# Arduino_DUE_V02b_1.net
KiCad netlist of a schematic drawn in Altium Designer
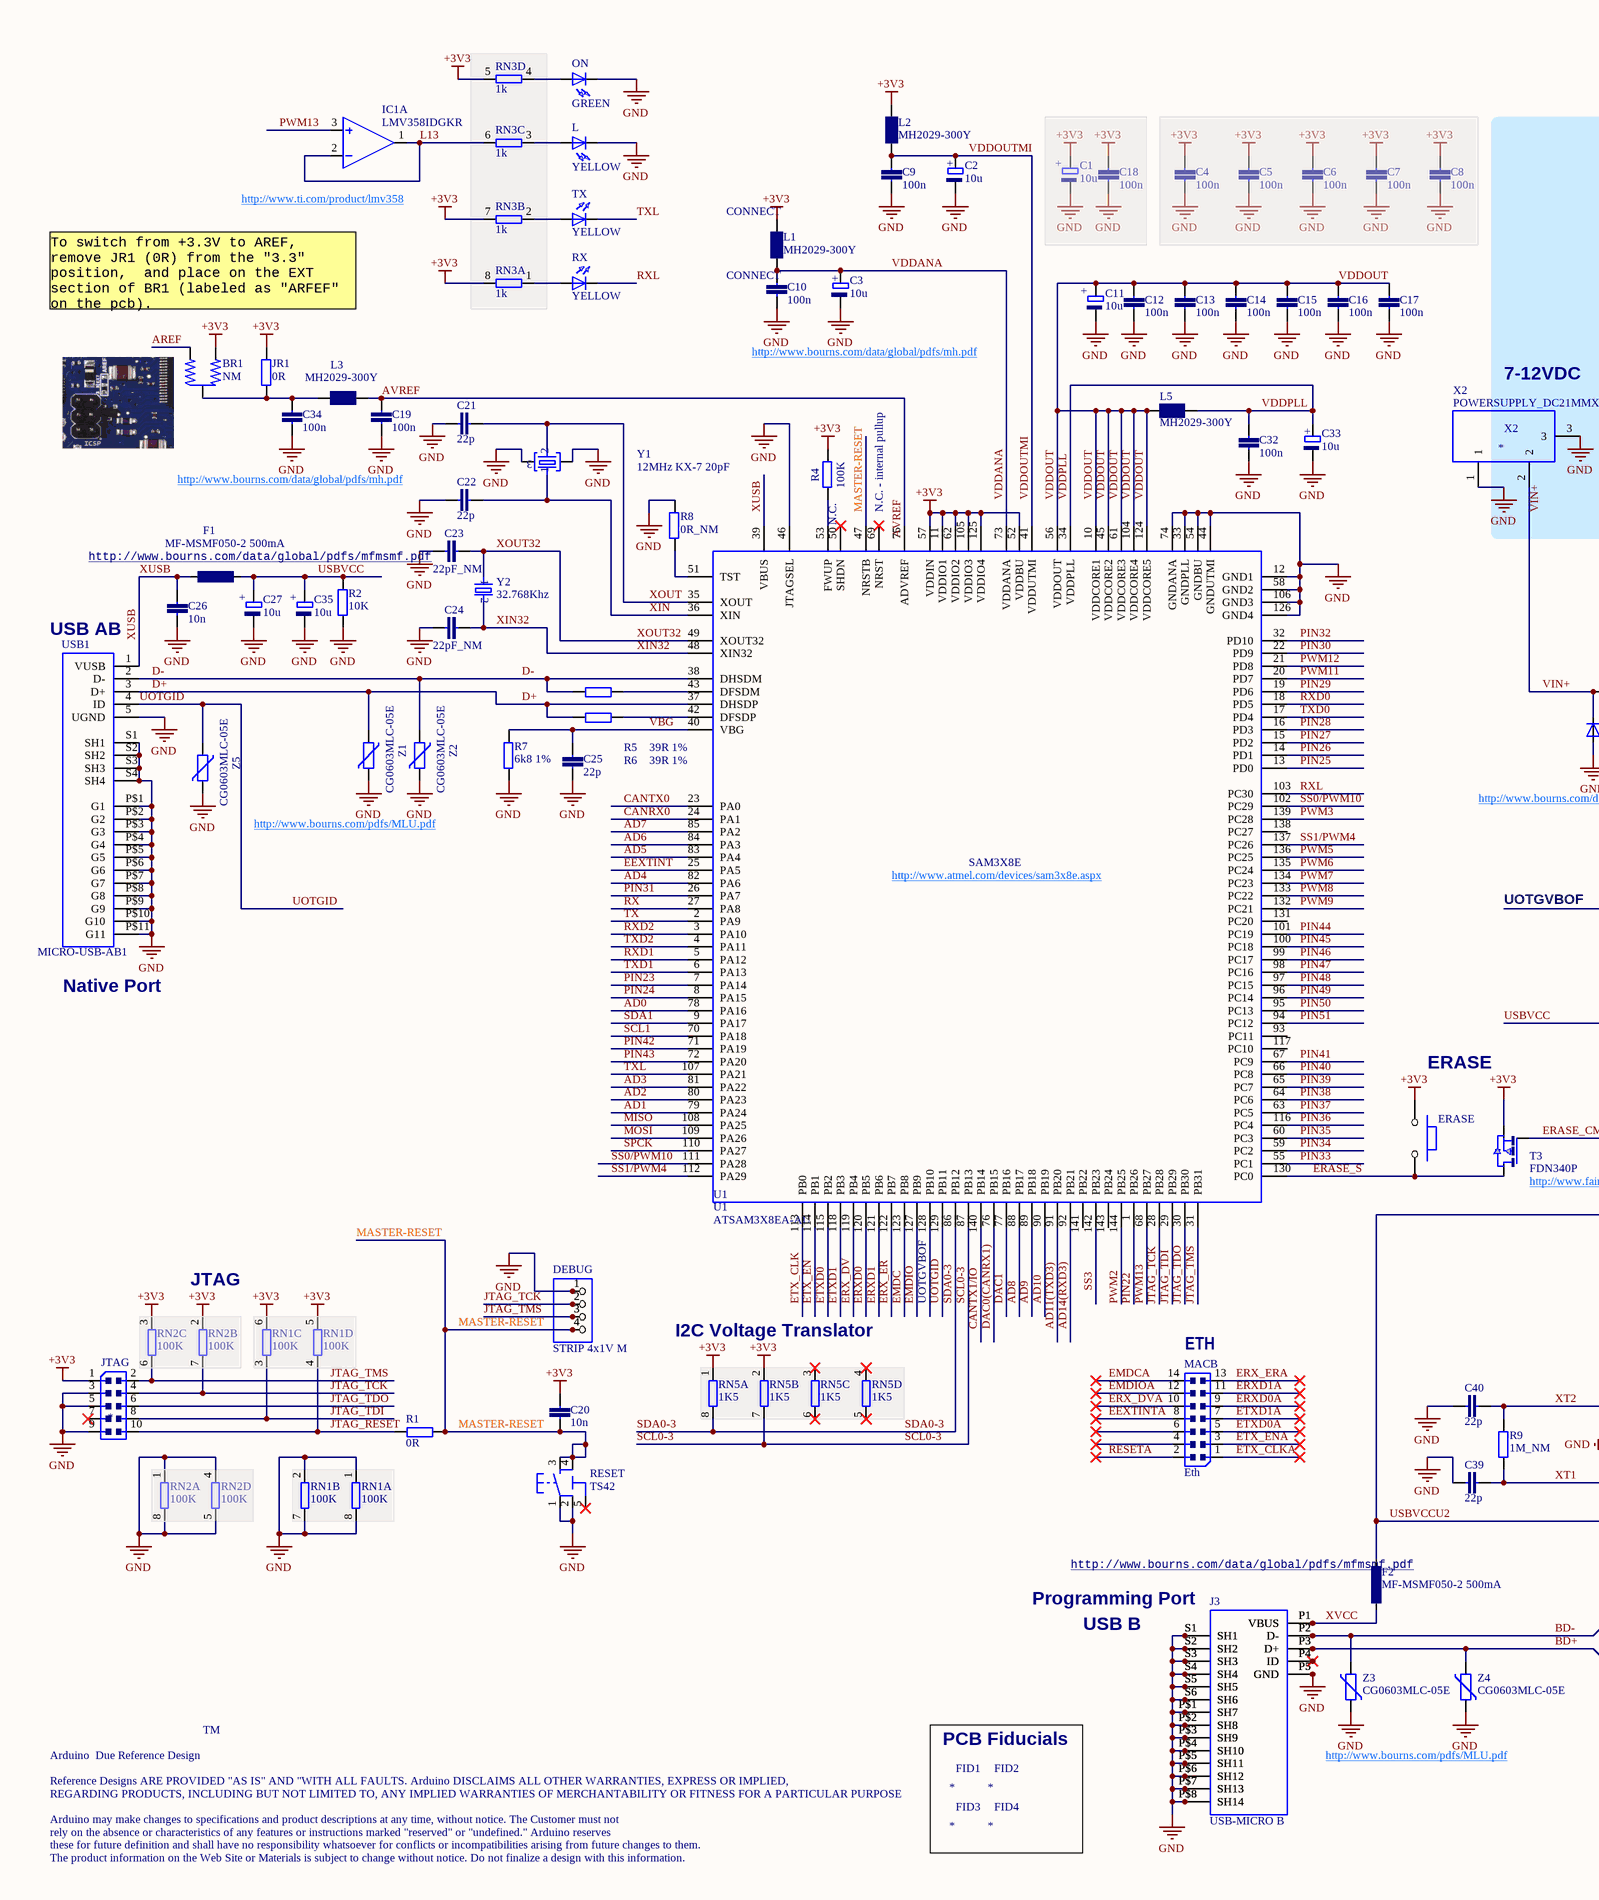
[diagram p0: Arduino_DUE_V02b_1.SchDoc, left]
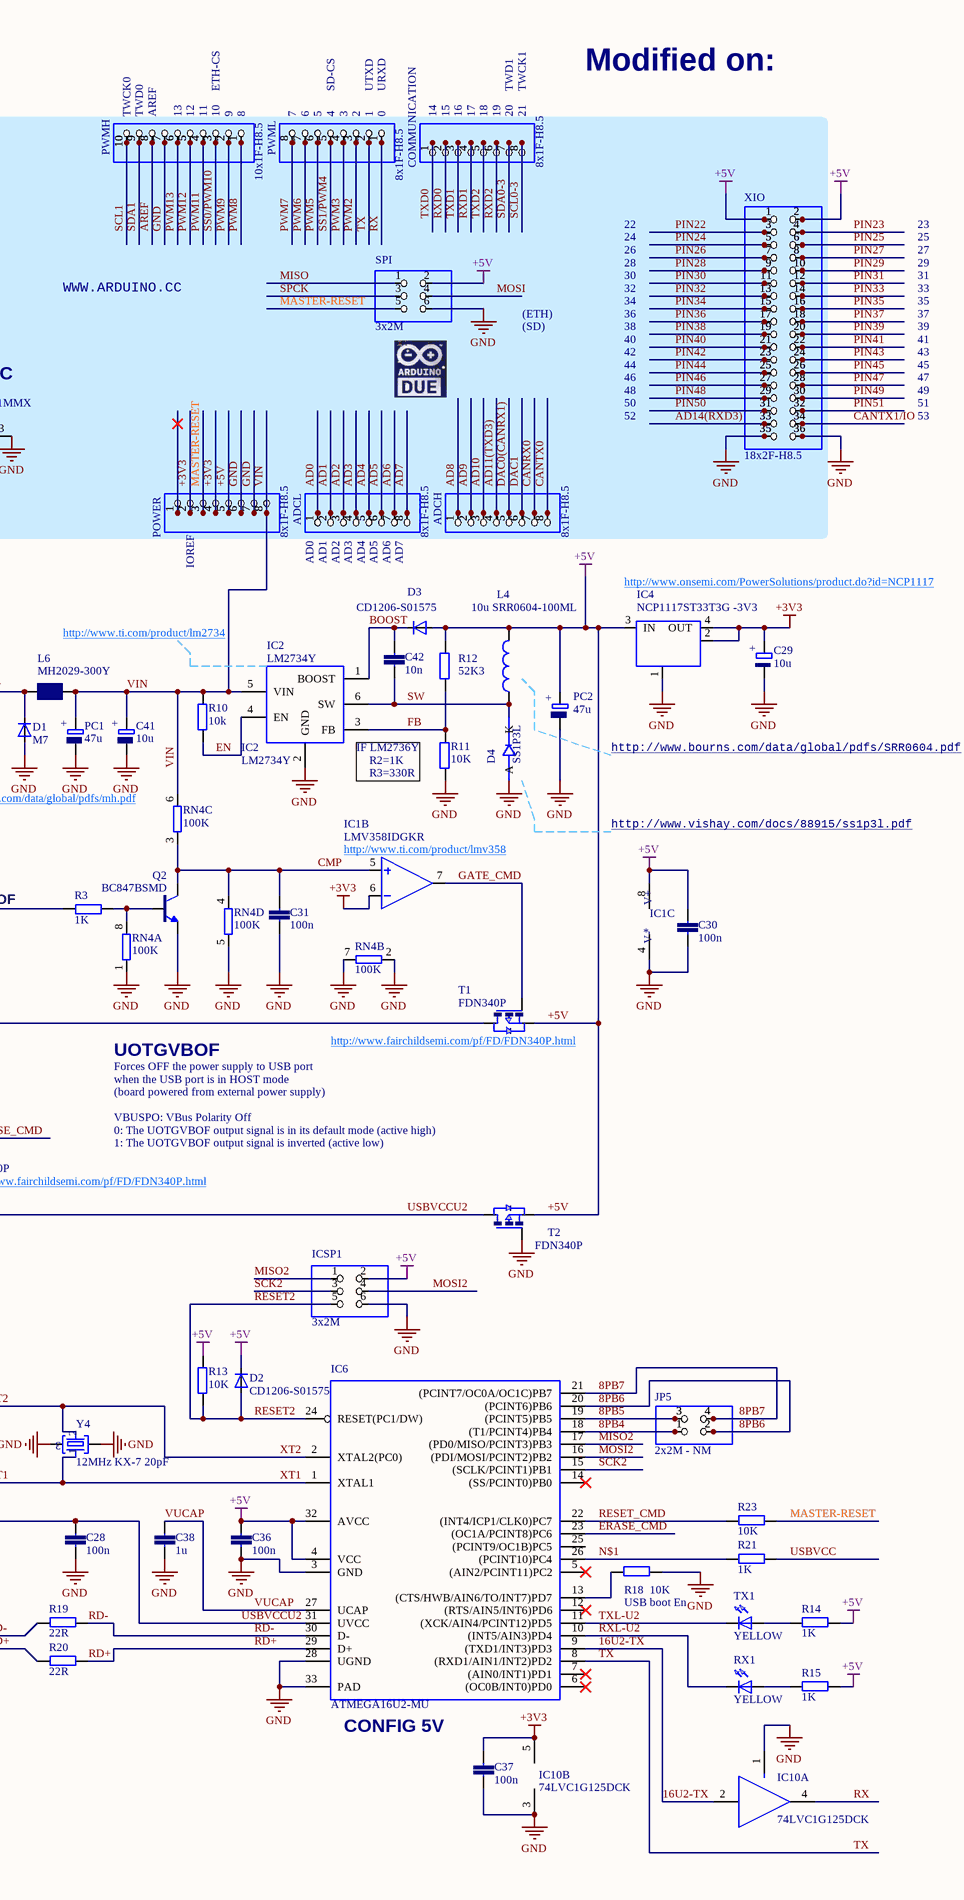
[diagram p1: Arduino_DUE_V02b_1.SchDoc, right]

(export (version "E")
  (design (tool "Eeschema 10.0.6"))
  (components
    (comp (ref "ADCH") (value "8x1F-H8.5") (footprint "1X08") (libsource (lib "SmartPrj") (part "PINHD-1X8")))
    (comp (ref "ADCL") (value "8x1F-H8.5") (footprint "1X08") (libsource (lib "SmartPrj") (part "PINHD-1X8")))
    (comp (ref "BR1") (value "NM") (footprint "J0402") (libsource (lib "bibaja") (part "J0402")))
    (comp (ref "C1") (value "10u") (footprint "SMC_B") (libsource (lib "") (part "CPOL-EUSMCB_1")))
    (comp (ref "C2") (value "10u") (footprint "SMC_B") (libsource (lib "rcl") (part "CPOL-EUSMCB")))
    (comp (ref "C3") (value "10u") (footprint "SMC_B") (libsource (lib "rcl") (part "CPOL-EUSMCB")))
    (comp (ref "C4") (value "100n") (footprint "C0402") (libsource (lib "") (part "C-EUC0402_2")))
    (comp (ref "C5") (value "100n") (footprint "C0402") (libsource (lib "") (part "C-EUC0402_2")))
    (comp (ref "C6") (value "100n") (footprint "C0402") (libsource (lib "") (part "C-EUC0402_2")))
    (comp (ref "C7") (value "100n") (footprint "C0402") (libsource (lib "") (part "C-EUC0402_2")))
    (comp (ref "C8") (value "100n") (footprint "C0402") (libsource (lib "") (part "C-EUC0402_2")))
    (comp (ref "C9") (value "100n") (footprint "C0402") (libsource (lib "") (part "C-EUC0402_2")))
    (comp (ref "C10") (value "100n") (footprint "C0402") (libsource (lib "") (part "C-EUC0402_2")))
    (comp (ref "C11") (value "10u") (footprint "SMC_B") (libsource (lib "") (part "CPOL-EUSMCB_1")))
    (comp (ref "C12") (value "100n") (footprint "C0402") (libsource (lib "") (part "C-EUC0402_2")))
    (comp (ref "C13") (value "100n") (footprint "C0402") (libsource (lib "") (part "C-EUC0402_2")))
    (comp (ref "C14") (value "100n") (footprint "C0402") (libsource (lib "") (part "C-EUC0402_2")))
    (comp (ref "C15") (value "100n") (footprint "C0402") (libsource (lib "") (part "C-EUC0402_2")))
    (comp (ref "C16") (value "100n") (footprint "C0402") (libsource (lib "") (part "C-EUC0402_2")))
    (comp (ref "C17") (value "100n") (footprint "C0402") (libsource (lib "") (part "C-EUC0402_2")))
    (comp (ref "C18") (value "100n") (footprint "C0402") (libsource (lib "") (part "C-EUC0402_2")))
    (comp (ref "C19") (value "100n") (footprint "C0402") (libsource (lib "") (part "C-EUC0402_1")))
    (comp (ref "C20") (value "10n") (footprint "C0402") (libsource (lib "") (part "C-EUC0402_1")))
    (comp (ref "C21") (value "22p") (footprint "C0402") (libsource (lib "") (part "C-EUC0402_3")))
    (comp (ref "C22") (value "22p") (footprint "C0402") (libsource (lib "") (part "C-EUC0402_3")))
    (comp (ref "C23") (value "22pF_NM") (footprint "C0402") (libsource (lib "") (part "C-EUC0402_3")))
    (comp (ref "C24") (value "22pF_NM") (footprint "C0402") (libsource (lib "") (part "C-EUC0402_3")))
    (comp (ref "C25") (value "22p") (footprint "C0402") (libsource (lib "SmartPrj") (part "C-EUC0402")))
    (comp (ref "C26") (value "10n") (footprint "C0402") (libsource (lib "SmartPrj") (part "C-EUC0402")))
    (comp (ref "C27") (value "10u") (footprint "SMC_B") (libsource (lib "") (part "CPOL-EUSMCB_1")))
    (comp (ref "C28") (value "100n") (footprint "C0402") (libsource (lib "SmartPrj") (part "C-EUC0402")))
    (comp (ref "C29") (value "10u") (footprint "SMC_B") (libsource (lib "") (part "CPOL-EUSMCB_1")))
    (comp (ref "C30") (value "100n") (footprint "C0402") (libsource (lib "") (part "C-EUC0402_2")))
    (comp (ref "C31") (value "100n") (footprint "C0402") (libsource (lib "") (part "C-EUC0402_2")))
    (comp (ref "C32") (value "100n") (footprint "C0402") (libsource (lib "") (part "C-EUC0402_2")))
    (comp (ref "C33") (value "10u") (footprint "SMC_B") (libsource (lib "rcl") (part "CPOL-EUSMCB")))
    (comp (ref "C34") (value "100n") (footprint "C0402") (libsource (lib "") (part "C-EUC0402_1")))
    (comp (ref "C35") (value "10u") (footprint "SMC_B") (libsource (lib "") (part "CPOL-EUSMCB_1")))
    (comp (ref "C36") (value "100n") (footprint "C0402") (libsource (lib "SmartPrj") (part "C-EUC0402")))
    (comp (ref "C37") (value "100n") (footprint "C0402") (libsource (lib "SmartPrj") (part "C-EUC0402")))
    (comp (ref "C38") (value "1u") (footprint "C0402") (libsource (lib "SmartPrj") (part "C-EUC0402")))
    (comp (ref "C39") (value "22p") (footprint "C0402") (libsource (lib "") (part "C-EUC0402_3")))
    (comp (ref "C40") (value "22p") (footprint "C0402") (libsource (lib "") (part "C-EUC0402_3")))
    (comp (ref "C41") (value "10u") (footprint "SMC_B") (libsource (lib "") (part "CPOL-EUSMCB_2")))
    (comp (ref "C42") (value "10n") (footprint "C0603-ROUND") (libsource (lib "SmartPrj") (part "C-EUC0603")))
    (comp (ref "COMMUNICATION")
      (value "8x1F-H8.5")
      (footprint "1X08")
      (libsource (lib "SmartPrj") (part "PINHD-1X8"))
    )
    (comp (ref "D1") (value "M7") (footprint "SMB") (libsource (lib "diode") (part "DIODE-SMB")))
    (comp (ref "D2")
      (value "CD1206-S01575")
      (footprint "MINIMELF")
      (libsource (lib "diode") (part "DIODE-MINIMELF"))
    )
    (comp (ref "D3")
      (value "CD1206-S01575")
      (footprint "MINIMELF")
      (libsource (lib "diode") (part "DIODE-MINIMELF"))
    )
    (comp (ref "D4") (value "SS1P3L") (footprint "DO220AAL") (libsource (lib "SmartPrj") (part "SS1P3L")))
    (comp (ref "DEBUG")
      (value "STRIP 4x1V M")
      (footprint "1X04")
      (libsource (lib "pinhead") (part "PINHD-1X4"))
    )
    (comp (ref "ERASE") (value "~") (footprint "SMD_157SW") (libsource (lib "SmartPrj") (part "MYSMD_PB157")))
    (comp (ref "F1")
      (value "MF-MSMF050-2 500mA")
      (footprint "L1812")
      (libsource (lib "") (part "L-EUL1812_1"))
    )
    (comp (ref "F2")
      (value "MF-MSMF050-2 500mA")
      (footprint "L1812")
      (libsource (lib "rcl") (part "L-EUL1812"))
    )
    (comp (ref "FID1")
      (value "*")
      (footprint "FIDUCIA-MOUNT")
      (libsource (lib "SmartPrj") (part "FIDUCIALMOUNT"))
    )
    (comp (ref "FID2")
      (value "*")
      (footprint "FIDUCIA-MOUNT")
      (libsource (lib "SmartPrj") (part "FIDUCIALMOUNT"))
    )
    (comp (ref "FID3")
      (value "*")
      (footprint "FIDUCIA-MOUNT")
      (libsource (lib "SmartPrj") (part "FIDUCIALMOUNT"))
    )
    (comp (ref "FID4")
      (value "*")
      (footprint "FIDUCIA-MOUNT")
      (libsource (lib "SmartPrj") (part "FIDUCIALMOUNT"))
    )
    (comp (ref "IC1")
      (value "LMV358IDGKR")
      (footprint "MSOP08")
      (libsource (lib "linear") (part "LMV358MMX"))
    )
    (comp (ref "IC2") (value "LM2734Y") (footprint "SOT23-6") (libsource (lib "SmartPrj") (part "LM2736Y")))
    (comp (ref "IC4")
      (value "NCP1117ST33T3G -3V3")
      (footprint "SOT223")
      (libsource (lib "linear") (part "MC33269ST-3.3T3"))
    )
    (comp (ref "IC6")
      (value "ATMEGA16U2-MU")
      (footprint "MLF32")
      (libsource (lib "SmartPrj") (part "ATMEGA16U2-MU"))
    )
    (comp (ref "IC10")
      (value "74LVC1G125DCK")
      (footprint "SC70-5")
      (libsource (lib "74xx-little-us") (part "74LVC1G125DCK"))
    )
    (comp (ref "ICSP1") (value "3x2M") (footprint "2X03") (libsource (lib "SmartPrj") (part "PINHD-2X3")))
    (comp (ref "J3")
      (value "USB-MICRO B")
      (footprint "CON2_USB_MICRO_B_AT")
      (libsource (lib "SmartPrj") (part "MYCON2_USB-MINI-B"))
    )
    (comp (ref "JP5") (value "2x2M - NM") (footprint "2X02") (libsource (lib "SmartPrj") (part "PINHD-2X2")))
    (comp (ref "JR1") (value "0R") (footprint "R0402") (libsource (lib "SmartPrj") (part "R-EU_R0402")))
    (comp (ref "JTAG")
      (value "*")
      (footprint "PINHEAD_2X05_127")
      (libsource (lib "Arduino_Wifi_shield_v018_tG") (part "PINHEAD_PINHD-2X5PASSO127"))
    )
    (comp (ref "L")
      (value "YELLOW")
      (footprint "CHIP-LED0805")
      (libsource (lib "") (part "LEDCHIP-LED0805_2"))
    )
    (comp (ref "L1") (value "MH2029-300Y") (footprint "0805") (libsource (lib "") (part "WE-CBF_0805_1")))
    (comp (ref "L2") (value "MH2029-300Y") (footprint "0805") (libsource (lib "") (part "WE-CBF_0805_1")))
    (comp (ref "L3") (value "MH2029-300Y") (footprint "0805") (libsource (lib "") (part "WE-CBF_0805_2")))
    (comp (ref "L4")
      (value "10u SRR0604-100ML")
      (footprint "SRR0604")
      (libsource (lib "SmartPrj") (part "L-USSRR0604"))
    )
    (comp (ref "L5") (value "MH2029-300Y") (footprint "0805") (libsource (lib "") (part "WE-CBF_0805_2")))
    (comp (ref "L6")
      (value "MH2029-300Y")
      (footprint "0805")
      (libsource (lib "wuerth-elektronik") (part "WE-CBF_0805"))
    )
    (comp (ref "MACB")
      (value "Eth")
      (footprint "PINHEAD_2X07_127")
      (libsource (lib "Arduino_Wifi_shield_v018_tG") (part "PINHEAD_PINHD-2X7PASSO127"))
    )
    (comp (ref "ON")
      (value "GREEN")
      (footprint "CHIP-LED0805")
      (libsource (lib "") (part "LEDCHIP-LED0805_2"))
    )
    (comp (ref "PC1") (value "47u") (footprint "PANASONIC_D") (libsource (lib "rcl") (part "CPOL-EUD")))
    (comp (ref "PC2") (value "47u") (footprint "PANASONIC_D") (libsource (lib "rcl") (part "CPOL-EUD")))
    (comp (ref "POWER")
      (value "8x1F-H8.5")
      (footprint "1X08")
      (libsource (lib "SmartPrj") (part "PINHD-1X8"))
    )
    (comp (ref "PWMH")
      (value "10x1F-H8.5")
      (footprint "1X10")
      (libsource (lib "SmartPrj") (part "PINHD-1X10"))
    )
    (comp (ref "PWML") (value "8x1F-H8.5") (footprint "1X08") (libsource (lib "SmartPrj") (part "PINHD-1X8")))
    (comp (ref "Q2")
      (value "BC847BSMD")
      (footprint "SOT23")
      (libsource (lib "transistor-npn") (part "BC847BSMD"))
    )
    (comp (ref "R1") (value "0R") (footprint "R0402") (libsource (lib "SmartPrj") (part "R-EU_R0402")))
    (comp (ref "R2") (value "10K") (footprint "R0402") (libsource (lib "") (part "R-EU_R0402_2")))
    (comp (ref "R3") (value "1K") (footprint "R0402") (libsource (lib "SmartPrj") (part "R-EU_R0402")))
    (comp (ref "R4") (value "100K") (footprint "R0402") (libsource (lib "") (part "R-EU_R0402_1")))
    (comp (ref "R5") (value "39R 1%") (footprint "R0402") (libsource (lib "SmartPrj") (part "R-EU_R0402")))
    (comp (ref "R6") (value "39R 1%") (footprint "R0402") (libsource (lib "SmartPrj") (part "R-EU_R0402")))
    (comp (ref "R7")
      (value "6k8 1%")
      (footprint "R0603-ROUND")
      (libsource (lib "SmartPrj") (part "R-EU_R0603"))
    )
    (comp (ref "R8") (value "0R_NM") (footprint "R0402") (libsource (lib "SmartPrj") (part "R-EU_R0402")))
    (comp (ref "R9") (value "1M_NM") (footprint "R0402") (libsource (lib "") (part "R-EU_R0402_1")))
    (comp (ref "R10") (value "10k") (footprint "R0402") (libsource (lib "SmartPrj") (part "R-EU_R0402")))
    (comp (ref "R11")
      (value "10K")
      (footprint "R0603-ROUND")
      (libsource (lib "SmartPrj") (part "R-EU_0603-RND"))
    )
    (comp (ref "R12")
      (value "52K3")
      (footprint "R0603-ROUND")
      (libsource (lib "SmartPrj") (part "R-EU_0603-RND"))
    )
    (comp (ref "R13") (value "10K") (footprint "R0402") (libsource (lib "") (part "R-EU_R0402_1")))
    (comp (ref "R14") (value "1K") (footprint "R0402") (libsource (lib "SmartPrj") (part "R-EU_R0402")))
    (comp (ref "R15") (value "1K") (footprint "R0402") (libsource (lib "SmartPrj") (part "R-EU_R0402")))
    (comp (ref "R18") (value "10K") (footprint "R0402") (libsource (lib "") (part "R-EU_R0402_1")))
    (comp (ref "R19") (value "22R") (footprint "R0402") (libsource (lib "SmartPrj") (part "R-EU_R0402")))
    (comp (ref "R20") (value "22R") (footprint "R0402") (libsource (lib "SmartPrj") (part "R-EU_R0402")))
    (comp (ref "R21") (value "1K") (footprint "R0402") (libsource (lib "") (part "R-EU_R0402_1")))
    (comp (ref "R23") (value "10K") (footprint "R0402") (libsource (lib "") (part "R-EU_R0402_1")))
    (comp (ref "RESET") (value "TS42") (footprint "TS42") (libsource (lib "SmartPrj") (part "TS42")))
    (comp (ref "RN1") (value "100K") (footprint "CAT16") (libsource (lib "") (part "4R-NCAT16_14")))
    (comp (ref "RN2") (value "100K") (footprint "CAT16") (libsource (lib "") (part "4R-NCAT16_11")))
    (comp (ref "RN3") (value "1k") (footprint "CAY16") (libsource (lib "") (part "4R-NCAY16_2")))
    (comp (ref "RN4") (value "100K") (footprint "CAT16") (libsource (lib "") (part "4R-NCAT16_9")))
    (comp (ref "RN5") (value "1K5") (footprint "CAT16") (libsource (lib "") (part "4R-NCAT16_5")))
    (comp (ref "RX")
      (value "YELLOW")
      (footprint "CHIP-LED0805")
      (libsource (lib "led") (part "LEDCHIP-LED0805"))
    )
    (comp (ref "RX1")
      (value "YELLOW")
      (footprint "CHIP-LED0805")
      (libsource (lib "") (part "LEDCHIP-LED0805_1"))
    )
    (comp (ref "SPI") (value "3x2M") (footprint "2X03") (libsource (lib "SmartPrj") (part "PINHD-2X3")))
    (comp (ref "T1") (value "FDN340P") (footprint "SOT-23") (libsource (lib "") (part "PMOSSOT23_1")))
    (comp (ref "T2") (value "FDN340P") (footprint "SOT-23") (libsource (lib "") (part "PMOSSOT23_2")))
    (comp (ref "T3") (value "FDN340P") (footprint "SOT-23") (libsource (lib "zetex") (part "PMOSSOT23")))
    (comp (ref "TX")
      (value "YELLOW")
      (footprint "CHIP-LED0805")
      (libsource (lib "led") (part "LEDCHIP-LED0805"))
    )
    (comp (ref "TX1")
      (value "YELLOW")
      (footprint "CHIP-LED0805")
      (libsource (lib "") (part "LEDCHIP-LED0805_1"))
    )
    (comp (ref "U1")
      (value "SAM3X8E")
      (footprint "LQFP144")
      (libsource (lib "SmartPrj") (part "ATSAM3X/AAU"))
    )
    (comp (ref "USB1")
      (value "MICRO-USB-AB1")
      (footprint "MCR-AB1-S-RA-SMT")
      (libsource (lib "SmartPrj") (part "MICRO_USB"))
    )
    (comp (ref "X2")
      (value "*")
      (footprint "POWERSUPPLY_DC-21MM")
      (libsource (lib "SmartPrj") (part "POWERSUPPLY_DC21MMX"))
    )
    (comp (ref "XIO")
      (value "18x2F-H8.5")
      (footprint "2X18")
      (libsource (lib "SmartPrj") (part "PINHD-2X18"))
    )
    (comp (ref "Y1")
      (value "12MHz KX-7 20pF")
      (footprint "CRYSTAL-3.2-2.5")
      (libsource (lib "SmartPrj") (part "CRYSTAL-3.2-2.5"))
    )
    (comp (ref "Y2")
      (value "32.768Khz")
      (footprint "RESONATOR_EPSON_FC_145")
      (libsource (lib "Arduino_Wifi_shield_v018_tG") (part "RESONATOR_EPSON_FC_145"))
    )
    (comp (ref "Y4")
      (value "12MHz KX-7 20pF")
      (footprint "CRYSTAL-3.2-2.5")
      (libsource (lib "") (part "CRYSTAL-3.2-2.5_1"))
    )
    (comp (ref "Z1")
      (value "CG0603MLC-05E")
      (footprint "CT/CN0603")
      (libsource (lib "") (part "VARISTORCN0603_1"))
    )
    (comp (ref "Z2")
      (value "CG0603MLC-05E")
      (footprint "CT/CN0603")
      (libsource (lib "") (part "VARISTORCN0603_1"))
    )
    (comp (ref "Z3")
      (value "CG0603MLC-05E")
      (footprint "CT/CN0603")
      (libsource (lib "varistor") (part "VARISTORCN0603"))
    )
    (comp (ref "Z4")
      (value "CG0603MLC-05E")
      (footprint "CT/CN0603")
      (libsource (lib "varistor") (part "VARISTORCN0603"))
    )
    (comp (ref "Z5")
      (value "CG0603MLC-05E")
      (footprint "CT/CN0603")
      (libsource (lib "") (part "VARISTORCN0603_1"))
    )
  )
  (nets
    (net (code "1") (name "+3V3") (class "Default")
      (node (ref "BR1") (pin "3") (pinfunction "2_3") (pintype "passive"))
      (node (ref "C1") (pin "+") (pinfunction "+_+") (pintype "passive"))
      (node (ref "C18") (pin "2") (pinfunction "2_2") (pintype "passive"))
      (node (ref "C20") (pin "2") (pinfunction "2_2") (pintype "passive"))
      (node (ref "C29") (pin "+") (pinfunction "+_+") (pintype "passive"))
      (node (ref "C37") (pin "1") (pinfunction "1_1") (pintype "passive"))
      (node (ref "C4") (pin "2") (pinfunction "2_2") (pintype "passive"))
      (node (ref "C5") (pin "2") (pinfunction "2_2") (pintype "passive"))
      (node (ref "C6") (pin "2") (pinfunction "2_2") (pintype "passive"))
      (node (ref "C7") (pin "2") (pinfunction "2_2") (pintype "passive"))
      (node (ref "C8") (pin "2") (pinfunction "2_2") (pintype "passive"))
      (node (ref "ERASE") (pin "1") (pinfunction "1_1") (pintype "passive"))
      (node (ref "IC1") (pin "6") (pinfunction "-IN_6") (pintype "passive"))
      (node (ref "IC10") (pin "5") (pinfunction "VCC_5") (pintype "passive"))
      (node (ref "IC4") (pin "2") (pinfunction "OUT@1_2") (pintype "passive"))
      (node (ref "IC4") (pin "4") (pinfunction "OUT_4") (pintype "passive"))
      (node (ref "JR1") (pin "1") (pinfunction "1_1") (pintype "passive"))
      (node (ref "JTAG") (pin "1") (pinfunction "1_1") (pintype "passive"))
      (node (ref "L1") (pin "1") (pinfunction "1_1") (pintype "passive"))
      (node (ref "L2") (pin "1") (pinfunction "1_1") (pintype "passive"))
      (node (ref "POWER") (pin "2") (pinfunction "2_2") (pintype "passive"))
      (node (ref "POWER") (pin "4") (pinfunction "4_4") (pintype "passive"))
      (node (ref "R4") (pin "2") (pinfunction "2_2") (pintype "passive"))
      (node (ref "RN1") (pin "5") (pinfunction "2_5") (pintype "passive"))
      (node (ref "RN1") (pin "6") (pinfunction "2_6") (pintype "passive"))
      (node (ref "RN2") (pin "2") (pinfunction "1_2") (pintype "passive"))
      (node (ref "RN2") (pin "3") (pinfunction "1_3") (pintype "passive"))
      (node (ref "RN3") (pin "5") (pinfunction "2_5") (pintype "passive"))
      (node (ref "RN3") (pin "7") (pinfunction "2_7") (pintype "passive"))
      (node (ref "RN3") (pin "8") (pinfunction "2_8") (pintype "passive"))
      (node (ref "RN5") (pin "1") (pinfunction "1_1") (pintype "passive"))
      (node (ref "RN5") (pin "2") (pinfunction "1_2") (pintype "passive"))
      (node (ref "T3") (pin "2") (pinfunction "S_2") (pintype "passive"))
      (node (ref "U1") (pin "105") (pinfunction "VDDIO3_105") (pintype "passive"))
      (node (ref "U1") (pin "11") (pinfunction "VDDIO1_11") (pintype "passive"))
      (node (ref "U1") (pin "125") (pinfunction "VDDIO4_125") (pintype "passive"))
      (node (ref "U1") (pin "52") (pinfunction "VDDBU_52") (pintype "passive"))
      (node (ref "U1") (pin "57") (pinfunction "VDDIN_57") (pintype "passive"))
      (node (ref "U1") (pin "62") (pinfunction "VDDIO2_62") (pintype "passive"))
    )
    (net (code "2") (name "+5V") (class "Default")
      (node (ref "C30") (pin "2") (pinfunction "2_2") (pintype "passive"))
      (node (ref "C36") (pin "1") (pinfunction "1_1") (pintype "passive"))
      (node (ref "D2") (pin "C") (pinfunction "C_C") (pintype "passive"))
      (node (ref "D3") (pin "A") (pinfunction "A_A") (pintype "passive"))
      (node (ref "IC1") (pin "8") (pinfunction "V+_8") (pintype "passive"))
      (node (ref "IC4") (pin "3") (pinfunction "IN_3") (pintype "passive"))
      (node (ref "IC6") (pin "32") (pinfunction "AVCC_32") (pintype "passive"))
      (node (ref "IC6") (pin "4") (pinfunction "VCC_4") (pintype "passive"))
      (node (ref "ICSP1") (pin "2") (pinfunction "2_2") (pintype "passive"))
      (node (ref "L4") (pin "P$2") (pinfunction "2_P$2") (pintype "passive"))
      (node (ref "PC2") (pin "+") (pinfunction "+_+") (pintype "passive"))
      (node (ref "POWER") (pin "5") (pinfunction "5_5") (pintype "passive"))
      (node (ref "R12") (pin "1") (pinfunction "1_1") (pintype "passive"))
      (node (ref "R13") (pin "2") (pinfunction "2_2") (pintype "passive"))
      (node (ref "R14") (pin "1") (pinfunction "1_1") (pintype "passive"))
      (node (ref "R15") (pin "1") (pinfunction "1_1") (pintype "passive"))
      (node (ref "SPI") (pin "2") (pinfunction "2_2") (pintype "passive"))
      (node (ref "T1") (pin "2") (pinfunction "S_2") (pintype "passive"))
      (node (ref "T2") (pin "2") (pinfunction "S_2") (pintype "passive"))
      (node (ref "XIO") (pin "1") (pinfunction "1_1") (pintype "passive"))
      (node (ref "XIO") (pin "2") (pinfunction "2_2") (pintype "passive"))
    )
    (net (code "3") (name "/8PB4") (class "Default")
      (node (ref "IC6") (pin "18") (pinfunction "(T1/PCINT4)PB4_18") (pintype "passive"))
      (node (ref "JP5") (pin "1") (pinfunction "1_1") (pintype "passive"))
    )
    (net (code "4") (name "/8PB5") (class "Default")
      (node (ref "IC6") (pin "19") (pinfunction "(PCINT5)PB5_19") (pintype "passive"))
      (node (ref "JP5") (pin "3") (pinfunction "3_3") (pintype "passive"))
    )
    (net (code "5") (name "/8PB6") (class "Default")
      (node (ref "IC6") (pin "20") (pinfunction "(PCINT6)PB6_20") (pintype "passive"))
      (node (ref "JP5") (pin "2") (pinfunction "2_2") (pintype "passive"))
    )
    (net (code "6") (name "/8PB7") (class "Default")
      (node (ref "IC6") (pin "21") (pinfunction "(PCINT7/OC0A/OC1C)PB7_21") (pintype "passive"))
      (node (ref "JP5") (pin "4") (pinfunction "4_4") (pintype "passive"))
    )
    (net (code "7") (name "/16U2-TX") (class "Default")
      (node (ref "IC10") (pin "2") (pinfunction "I_2") (pintype "passive"))
      (node (ref "IC6") (pin "9") (pinfunction "(TXD1/INT3)PD3_9") (pintype "passive"))
    )
    (net (code "8") (name "/AD0") (class "Default")
      (node (ref "ADCL") (pin "1") (pinfunction "1_1") (pintype "passive"))
      (node (ref "U1") (pin "78") (pinfunction "PA16_78") (pintype "passive"))
    )
    (net (code "9") (name "/AD1") (class "Default")
      (node (ref "ADCL") (pin "2") (pinfunction "2_2") (pintype "passive"))
      (node (ref "U1") (pin "79") (pinfunction "PA24_79") (pintype "passive"))
    )
    (net (code "10") (name "/AD2") (class "Default")
      (node (ref "ADCL") (pin "3") (pinfunction "3_3") (pintype "passive"))
      (node (ref "U1") (pin "80") (pinfunction "PA23_80") (pintype "passive"))
    )
    (net (code "11") (name "/AD3") (class "Default")
      (node (ref "ADCL") (pin "4") (pinfunction "4_4") (pintype "passive"))
      (node (ref "U1") (pin "81") (pinfunction "PA22_81") (pintype "passive"))
    )
    (net (code "12") (name "/AD4") (class "Default")
      (node (ref "ADCL") (pin "5") (pinfunction "5_5") (pintype "passive"))
      (node (ref "U1") (pin "82") (pinfunction "PA6_82") (pintype "passive"))
    )
    (net (code "13") (name "/AD5") (class "Default")
      (node (ref "ADCL") (pin "6") (pinfunction "6_6") (pintype "passive"))
      (node (ref "U1") (pin "83") (pinfunction "PA4_83") (pintype "passive"))
    )
    (net (code "14") (name "/AD6") (class "Default")
      (node (ref "ADCL") (pin "7") (pinfunction "7_7") (pintype "passive"))
      (node (ref "U1") (pin "84") (pinfunction "PA3_84") (pintype "passive"))
    )
    (net (code "15") (name "/AD7") (class "Default")
      (node (ref "ADCL") (pin "8") (pinfunction "8_8") (pintype "passive"))
      (node (ref "U1") (pin "85") (pinfunction "PA2_85") (pintype "passive"))
    )
    (net (code "16") (name "/AD8") (class "Default")
      (node (ref "ADCH") (pin "1") (pinfunction "1_1") (pintype "passive"))
      (node (ref "U1") (pin "88") (pinfunction "PB17_88") (pintype "passive"))
    )
    (net (code "17") (name "/AD9") (class "Default")
      (node (ref "ADCH") (pin "2") (pinfunction "2_2") (pintype "passive"))
      (node (ref "U1") (pin "89") (pinfunction "PB18_89") (pintype "passive"))
    )
    (net (code "18") (name "/AD10") (class "Default")
      (node (ref "ADCH") (pin "3") (pinfunction "3_3") (pintype "passive"))
      (node (ref "U1") (pin "90") (pinfunction "PB19_90") (pintype "passive"))
    )
    (net (code "19") (name "/AD11(TXD3)") (class "Default")
      (node (ref "ADCH") (pin "4") (pinfunction "4_4") (pintype "passive"))
      (node (ref "U1") (pin "91") (pinfunction "PB20_91") (pintype "passive"))
    )
    (net (code "20") (name "/AD14(RXD3)") (class "Default")
      (node (ref "U1") (pin "92") (pinfunction "PB21_92") (pintype "passive"))
      (node (ref "XIO") (pin "33") (pinfunction "33_33") (pintype "passive"))
    )
    (net (code "21") (name "/AREF") (class "Default")
      (node (ref "BR1") (pin "1") (pinfunction "1_1") (pintype "passive"))
      (node (ref "PWMH") (pin "8") (pinfunction "8_8") (pintype "passive"))
    )
    (net (code "22") (name "/AVREF") (class "Default")
      (node (ref "C19") (pin "2") (pinfunction "2_2") (pintype "passive"))
      (node (ref "L3") (pin "2") (pinfunction "2_2") (pintype "passive"))
      (node (ref "U1") (pin "75") (pinfunction "ADVREF_75") (pintype "passive"))
    )
    (net (code "23") (name "/BD+") (class "Default")
      (node (ref "J3") (pin "P3") (pinfunction "D+_P3") (pintype "passive"))
      (node (ref "R20") (pin "2") (pinfunction "2_2") (pintype "passive"))
      (node (ref "Z4") (pin "2") (pinfunction "2_2") (pintype "passive"))
    )
    (net (code "24") (name "/BD-") (class "Default")
      (node (ref "J3") (pin "P2") (pinfunction "D-_P2") (pintype "passive"))
      (node (ref "R19") (pin "2") (pinfunction "2_2") (pintype "passive"))
      (node (ref "Z3") (pin "2") (pinfunction "2_2") (pintype "passive"))
    )
    (net (code "25") (name "/BOOST") (class "Default")
      (node (ref "C42") (pin "1") (pinfunction "1_1") (pintype "passive"))
      (node (ref "D3") (pin "C") (pinfunction "C_C") (pintype "passive"))
      (node (ref "IC2") (pin "1") (pinfunction "BOOST_1") (pintype "passive"))
    )
    (net (code "26") (name "/CANRX0") (class "Default")
      (node (ref "ADCH") (pin "7") (pinfunction "7_7") (pintype "passive"))
      (node (ref "U1") (pin "24") (pinfunction "PA1_24") (pintype "passive"))
    )
    (net (code "27") (name "/CANTX0") (class "Default")
      (node (ref "ADCH") (pin "8") (pinfunction "8_8") (pintype "passive"))
      (node (ref "U1") (pin "23") (pinfunction "PA0_23") (pintype "passive"))
    )
    (net (code "28") (name "/CANTX1{slash}IO") (class "Default")
      (node (ref "U1") (pin "140") (pinfunction "PB14_140") (pintype "passive"))
      (node (ref "XIO") (pin "34") (pinfunction "34_34") (pintype "passive"))
    )
    (net (code "29") (name "/CMP") (class "Default")
      (node (ref "C31") (pin "2") (pinfunction "2_2") (pintype "passive"))
      (node (ref "IC1") (pin "5") (pinfunction "+IN_5") (pintype "passive"))
      (node (ref "Q2") (pin "3") (pinfunction "C_3") (pintype "passive"))
      (node (ref "RN4") (pin "3") (pinfunction "1_3") (pintype "passive"))
      (node (ref "RN4") (pin "4") (pinfunction "1_4") (pintype "passive"))
    )
    (net (code "30") (name "/D+") (class "Default")
      (node (ref "R6") (pin "1") (pinfunction "1_1") (pintype "passive"))
      (node (ref "U1") (pin "37") (pinfunction "DHSDP_37") (pintype "passive"))
      (node (ref "USB1") (pin "3") (pinfunction "D+_3") (pintype "passive"))
      (node (ref "Z1") (pin "1") (pinfunction "1_1") (pintype "passive"))
    )
    (net (code "31") (name "/D-") (class "Default")
      (node (ref "R5") (pin "1") (pinfunction "1_1") (pintype "passive"))
      (node (ref "U1") (pin "38") (pinfunction "DHSDM_38") (pintype "passive"))
      (node (ref "USB1") (pin "2") (pinfunction "D-_2") (pintype "passive"))
      (node (ref "Z2") (pin "1") (pinfunction "1_1") (pintype "passive"))
    )
    (net (code "32") (name "/DAC0(CANRX1)") (class "Default")
      (node (ref "ADCH") (pin "5") (pinfunction "5_5") (pintype "passive"))
      (node (ref "U1") (pin "76") (pinfunction "PB15_76") (pintype "passive"))
    )
    (net (code "33") (name "/DAC1") (class "Default")
      (node (ref "ADCH") (pin "6") (pinfunction "6_6") (pintype "passive"))
      (node (ref "U1") (pin "77") (pinfunction "PB16_77") (pintype "passive"))
    )
    (net (code "34") (name "/EEXTINT") (class "Default")
      (node (ref "U1") (pin "25") (pinfunction "PA5_25") (pintype "passive"))
    )
    (net (code "35") (name "/EEXTINTA") (class "Default")
      (node (ref "MACB") (pin "8") (pinfunction "8_8") (pintype "passive+no_connect"))
    )
    (net (code "36") (name "/EMDC") (class "Default")
      (node (ref "U1") (pin "123") (pinfunction "PB8_123") (pintype "passive"))
    )
    (net (code "37") (name "/EMDCA") (class "Default")
      (node (ref "MACB") (pin "14") (pinfunction "14_14") (pintype "passive+no_connect"))
    )
    (net (code "38") (name "/EMDIO") (class "Default")
      (node (ref "U1") (pin "127") (pinfunction "PB9_127") (pintype "passive"))
    )
    (net (code "39") (name "/EMDIOA") (class "Default")
      (node (ref "MACB") (pin "12") (pinfunction "13_12") (pintype "passive+no_connect"))
    )
    (net (code "40") (name "/EN") (class "Default")
      (node (ref "IC2") (pin "4") (pinfunction "EN_4") (pintype "passive"))
      (node (ref "R10") (pin "2") (pinfunction "2_2") (pintype "passive"))
    )
    (net (code "41") (name "/ERASE_CMD") (class "Default")
      (node (ref "IC6") (pin "23") (pinfunction "(OC1A/PCINT8)PC6_23") (pintype "passive"))
      (node (ref "T3") (pin "3") (pinfunction "G_3") (pintype "passive"))
    )
    (net (code "42") (name "/ERASE_S") (class "Default")
      (node (ref "ERASE") (pin "2") (pinfunction "2_2") (pintype "passive"))
      (node (ref "T3") (pin "1") (pinfunction "D_1") (pintype "passive"))
      (node (ref "U1") (pin "130") (pinfunction "PC0_130") (pintype "passive"))
    )
    (net (code "43") (name "/ERXD0") (class "Default")
      (node (ref "U1") (pin "120") (pinfunction "PB5_120") (pintype "passive"))
    )
    (net (code "44") (name "/ERXD0A") (class "Default")
      (node (ref "MACB") (pin "9") (pinfunction "9_9") (pintype "passive+no_connect"))
    )
    (net (code "45") (name "/ERXD1") (class "Default")
      (node (ref "U1") (pin "121") (pinfunction "PB6_121") (pintype "passive"))
    )
    (net (code "46") (name "/ERXD1A") (class "Default")
      (node (ref "MACB") (pin "11") (pinfunction "11_11") (pintype "passive+no_connect"))
    )
    (net (code "47") (name "/ERX_DV") (class "Default")
      (node (ref "U1") (pin "119") (pinfunction "PB4_119") (pintype "passive"))
    )
    (net (code "48") (name "/ERX_DVA") (class "Default")
      (node (ref "MACB") (pin "10") (pinfunction "10_10") (pintype "passive+no_connect"))
    )
    (net (code "49") (name "/ERX_ER") (class "Default")
      (node (ref "U1") (pin "122") (pinfunction "PB7_122") (pintype "passive"))
    )
    (net (code "50") (name "/ERX_ERA") (class "Default")
      (node (ref "MACB") (pin "13") (pinfunction "12_13") (pintype "passive+no_connect"))
    )
    (net (code "51") (name "/ETXD0") (class "Default")
      (node (ref "U1") (pin "115") (pinfunction "PB2_115") (pintype "passive"))
    )
    (net (code "52") (name "/ETXD0A") (class "Default")
      (node (ref "MACB") (pin "5") (pinfunction "5_5") (pintype "passive+no_connect"))
    )
    (net (code "53") (name "/ETXD1") (class "Default")
      (node (ref "U1") (pin "118") (pinfunction "PB3_118") (pintype "passive"))
    )
    (net (code "54") (name "/ETXD1A") (class "Default")
      (node (ref "MACB") (pin "7") (pinfunction "7_7") (pintype "passive+no_connect"))
    )
    (net (code "55") (name "/ETX_CLK") (class "Default")
      (node (ref "U1") (pin "113") (pinfunction "PB0_113") (pintype "passive"))
    )
    (net (code "56") (name "/ETX_CLKA") (class "Default")
      (node (ref "MACB") (pin "1") (pinfunction "1_1") (pintype "passive+no_connect"))
    )
    (net (code "57") (name "/ETX_EN") (class "Default")
      (node (ref "U1") (pin "114") (pinfunction "PB1_114") (pintype "passive"))
    )
    (net (code "58") (name "/ETX_ENA") (class "Default")
      (node (ref "MACB") (pin "3") (pinfunction "3_3") (pintype "passive+no_connect"))
    )
    (net (code "59") (name "/FB") (class "Default")
      (node (ref "IC2") (pin "3") (pinfunction "FB_3") (pintype "passive"))
      (node (ref "R11") (pin "1") (pinfunction "1_1") (pintype "passive"))
      (node (ref "R12") (pin "2") (pinfunction "2_2") (pintype "passive"))
    )
    (net (code "60") (name "/GATE_CMD") (class "Default")
      (node (ref "IC1") (pin "7") (pinfunction "OUT_7") (pintype "passive"))
      (node (ref "T1") (pin "3") (pinfunction "G_3") (pintype "passive"))
    )
    (net (code "61") (name "/JTAG_RESET") (class "Default")
      (node (ref "JTAG") (pin "10") (pinfunction "10_10") (pintype "passive"))
      (node (ref "R1") (pin "1") (pinfunction "1_1") (pintype "passive"))
      (node (ref "RN1") (pin "4") (pinfunction "1_4") (pintype "passive"))
    )
    (net (code "62") (name "/JTAG_TCK") (class "Default")
      (node (ref "DEBUG") (pin "2") (pinfunction "2_2") (pintype "passive"))
      (node (ref "JTAG") (pin "4") (pinfunction "4_4") (pintype "passive"))
      (node (ref "RN2") (pin "7") (pinfunction "2_7") (pintype "passive"))
      (node (ref "U1") (pin "28") (pinfunction "PB28_28") (pintype "passive"))
    )
    (net (code "63") (name "/JTAG_TDI") (class "Default")
      (node (ref "JTAG") (pin "8") (pinfunction "8_8") (pintype "passive"))
      (node (ref "RN1") (pin "3") (pinfunction "1_3") (pintype "passive"))
      (node (ref "U1") (pin "29") (pinfunction "PB29_29") (pintype "passive"))
    )
    (net (code "64") (name "/JTAG_TDO") (class "Default")
      (node (ref "JTAG") (pin "6") (pinfunction "6_6") (pintype "passive"))
      (node (ref "U1") (pin "30") (pinfunction "PB30_30") (pintype "passive"))
    )
    (net (code "65") (name "/JTAG_TMS") (class "Default")
      (node (ref "DEBUG") (pin "3") (pinfunction "3_3") (pintype "passive"))
      (node (ref "JTAG") (pin "2") (pinfunction "2_2") (pintype "passive"))
      (node (ref "RN2") (pin "6") (pinfunction "2_6") (pintype "passive"))
      (node (ref "U1") (pin "31") (pinfunction "PB31_31") (pintype "passive"))
    )
    (net (code "66") (name "/L13") (class "Default")
      (node (ref "IC1") (pin "1") (pinfunction "OUT_1") (pintype "passive"))
      (node (ref "IC1") (pin "2") (pinfunction "-IN_2") (pintype "passive"))
      (node (ref "RN3") (pin "6") (pinfunction "2_6") (pintype "passive"))
    )
    (net (code "67") (name "/MASTER-RESET") (class "Default")
      (node (ref "C20") (pin "1") (pinfunction "1_1") (pintype "passive"))
      (node (ref "DEBUG") (pin "4") (pinfunction "4_4") (pintype "passive"))
      (node (ref "POWER") (pin "3") (pinfunction "3_3") (pintype "passive"))
      (node (ref "R1") (pin "2") (pinfunction "2_2") (pintype "passive"))
      (node (ref "R23") (pin "2") (pinfunction "2_2") (pintype "passive"))
      (node (ref "RESET") (pin "3") (pinfunction "3_3") (pintype "passive"))
      (node (ref "RESET") (pin "4") (pinfunction "4_4") (pintype "passive"))
      (node (ref "SPI") (pin "5") (pinfunction "5_5") (pintype "passive"))
      (node (ref "U1") (pin "47") (pinfunction "NRSTB_47") (pintype "passive"))
    )
    (net (code "68") (name "/MISO") (class "Default")
      (node (ref "SPI") (pin "1") (pinfunction "1_1") (pintype "passive"))
      (node (ref "U1") (pin "108") (pinfunction "PA25_108") (pintype "passive"))
    )
    (net (code "69") (name "/MISO2") (class "Default")
      (node (ref "IC6") (pin "17") (pinfunction "(PD0/MISO/PCINT3)PB3_17") (pintype "passive"))
      (node (ref "ICSP1") (pin "1") (pinfunction "1_1") (pintype "passive"))
    )
    (net (code "70") (name "/MOSI") (class "Default")
      (node (ref "SPI") (pin "4") (pinfunction "4_4") (pintype "passive"))
      (node (ref "U1") (pin "109") (pinfunction "PA26_109") (pintype "passive"))
    )
    (net (code "71") (name "/MOSI2") (class "Default")
      (node (ref "IC6") (pin "16") (pinfunction "(PDI/MOSI/PCINT2)PB2_16") (pintype "passive"))
      (node (ref "ICSP1") (pin "4") (pinfunction "4_4") (pintype "passive"))
    )
    (net (code "72") (name "/N$1") (class "Default")
      (node (ref "IC6") (pin "26") (pinfunction "(PCINT10)PC4_26") (pintype "passive"))
      (node (ref "R21") (pin "1") (pinfunction "1_1") (pintype "passive"))
    )
    (net (code "73") (name "/PIN22") (class "Default")
      (node (ref "U1") (pin "1") (pinfunction "PB26_1") (pintype "passive"))
      (node (ref "XIO") (pin "3") (pinfunction "3_3") (pintype "passive"))
    )
    (net (code "74") (name "/PIN23") (class "Default")
      (node (ref "U1") (pin "7") (pinfunction "PA14_7") (pintype "passive"))
      (node (ref "XIO") (pin "4") (pinfunction "4_4") (pintype "passive"))
    )
    (net (code "75") (name "/PIN24") (class "Default")
      (node (ref "U1") (pin "8") (pinfunction "PA15_8") (pintype "passive"))
      (node (ref "XIO") (pin "5") (pinfunction "5_5") (pintype "passive"))
    )
    (net (code "76") (name "/PIN25") (class "Default")
      (node (ref "U1") (pin "13") (pinfunction "PD0_13") (pintype "passive"))
      (node (ref "XIO") (pin "6") (pinfunction "6_6") (pintype "passive"))
    )
    (net (code "77") (name "/PIN26") (class "Default")
      (node (ref "U1") (pin "14") (pinfunction "PD1_14") (pintype "passive"))
      (node (ref "XIO") (pin "7") (pinfunction "7_7") (pintype "passive"))
    )
    (net (code "78") (name "/PIN27") (class "Default")
      (node (ref "U1") (pin "15") (pinfunction "PD2_15") (pintype "passive"))
      (node (ref "XIO") (pin "8") (pinfunction "8_8") (pintype "passive"))
    )
    (net (code "79") (name "/PIN28") (class "Default")
      (node (ref "U1") (pin "16") (pinfunction "PD3_16") (pintype "passive"))
      (node (ref "XIO") (pin "9") (pinfunction "9_9") (pintype "passive"))
    )
    (net (code "80") (name "/PIN29") (class "Default")
      (node (ref "U1") (pin "19") (pinfunction "PD6_19") (pintype "passive"))
      (node (ref "XIO") (pin "10") (pinfunction "10_10") (pintype "passive"))
    )
    (net (code "81") (name "/PIN30") (class "Default")
      (node (ref "U1") (pin "22") (pinfunction "PD9_22") (pintype "passive"))
      (node (ref "XIO") (pin "11") (pinfunction "11_11") (pintype "passive"))
    )
    (net (code "82") (name "/PIN31") (class "Default")
      (node (ref "U1") (pin "26") (pinfunction "PA7_26") (pintype "passive"))
      (node (ref "XIO") (pin "12") (pinfunction "12_12") (pintype "passive"))
    )
    (net (code "83") (name "/PIN32") (class "Default")
      (node (ref "U1") (pin "32") (pinfunction "PD10_32") (pintype "passive"))
      (node (ref "XIO") (pin "13") (pinfunction "13_13") (pintype "passive"))
    )
    (net (code "84") (name "/PIN33") (class "Default")
      (node (ref "U1") (pin "55") (pinfunction "PC1_55") (pintype "passive"))
      (node (ref "XIO") (pin "14") (pinfunction "14_14") (pintype "passive"))
    )
    (net (code "85") (name "/PIN34") (class "Default")
      (node (ref "U1") (pin "59") (pinfunction "PC2_59") (pintype "passive"))
      (node (ref "XIO") (pin "15") (pinfunction "15_15") (pintype "passive"))
    )
    (net (code "86") (name "/PIN35") (class "Default")
      (node (ref "U1") (pin "60") (pinfunction "PC3_60") (pintype "passive"))
      (node (ref "XIO") (pin "16") (pinfunction "16_16") (pintype "passive"))
    )
    (net (code "87") (name "/PIN36") (class "Default")
      (node (ref "U1") (pin "116") (pinfunction "PC4_116") (pintype "passive"))
      (node (ref "XIO") (pin "17") (pinfunction "17_17") (pintype "passive"))
    )
    (net (code "88") (name "/PIN37") (class "Default")
      (node (ref "U1") (pin "63") (pinfunction "PC5_63") (pintype "passive"))
      (node (ref "XIO") (pin "18") (pinfunction "18_18") (pintype "passive"))
    )
    (net (code "89") (name "/PIN38") (class "Default")
      (node (ref "U1") (pin "64") (pinfunction "PC6_64") (pintype "passive"))
      (node (ref "XIO") (pin "19") (pinfunction "19_19") (pintype "passive"))
    )
    (net (code "90") (name "/PIN39") (class "Default")
      (node (ref "U1") (pin "65") (pinfunction "PC7_65") (pintype "passive"))
      (node (ref "XIO") (pin "20") (pinfunction "20_20") (pintype "passive"))
    )
    (net (code "91") (name "/PIN40") (class "Default")
      (node (ref "U1") (pin "66") (pinfunction "PC8_66") (pintype "passive"))
      (node (ref "XIO") (pin "21") (pinfunction "21_21") (pintype "passive"))
    )
    (net (code "92") (name "/PIN41") (class "Default")
      (node (ref "U1") (pin "67") (pinfunction "PC9_67") (pintype "passive"))
      (node (ref "XIO") (pin "22") (pinfunction "22_22") (pintype "passive"))
    )
    (net (code "93") (name "/PIN42") (class "Default")
      (node (ref "U1") (pin "71") (pinfunction "PA19_71") (pintype "passive"))
      (node (ref "XIO") (pin "23") (pinfunction "23_23") (pintype "passive"))
    )
    (net (code "94") (name "/PIN43") (class "Default")
      (node (ref "U1") (pin "72") (pinfunction "PA20_72") (pintype "passive"))
      (node (ref "XIO") (pin "24") (pinfunction "24_24") (pintype "passive"))
    )
    (net (code "95") (name "/PIN44") (class "Default")
      (node (ref "U1") (pin "101") (pinfunction "PC19_101") (pintype "passive"))
      (node (ref "XIO") (pin "25") (pinfunction "25_25") (pintype "passive"))
    )
    (net (code "96") (name "/PIN45") (class "Default")
      (node (ref "U1") (pin "100") (pinfunction "PC18_100") (pintype "passive"))
      (node (ref "XIO") (pin "26") (pinfunction "26_26") (pintype "passive"))
    )
    (net (code "97") (name "/PIN46") (class "Default")
      (node (ref "U1") (pin "99") (pinfunction "PC17_99") (pintype "passive"))
      (node (ref "XIO") (pin "27") (pinfunction "27_27") (pintype "passive"))
    )
    (net (code "98") (name "/PIN47") (class "Default")
      (node (ref "U1") (pin "98") (pinfunction "PC16_98") (pintype "passive"))
      (node (ref "XIO") (pin "28") (pinfunction "28_28") (pintype "passive"))
    )
    (net (code "99") (name "/PIN48") (class "Default")
      (node (ref "U1") (pin "97") (pinfunction "PC15_97") (pintype "passive"))
      (node (ref "XIO") (pin "29") (pinfunction "29_29") (pintype "passive"))
    )
    (net (code "100") (name "/PIN49") (class "Default")
      (node (ref "U1") (pin "96") (pinfunction "PC14_96") (pintype "passive"))
      (node (ref "XIO") (pin "30") (pinfunction "30_30") (pintype "passive"))
    )
    (net (code "101") (name "/PIN50") (class "Default")
      (node (ref "U1") (pin "95") (pinfunction "PC13_95") (pintype "passive"))
      (node (ref "XIO") (pin "31") (pinfunction "31_31") (pintype "passive"))
    )
    (net (code "102") (name "/PIN51") (class "Default")
      (node (ref "U1") (pin "94") (pinfunction "PC12_94") (pintype "passive"))
      (node (ref "XIO") (pin "32") (pinfunction "32_32") (pintype "passive"))
    )
    (net (code "103") (name "/PWM2") (class "Default")
      (node (ref "PWML") (pin "3") (pinfunction "3_3") (pintype "passive"))
      (node (ref "U1") (pin "144") (pinfunction "PB25_144") (pintype "passive"))
    )
    (net (code "104") (name "/PWM3") (class "Default")
      (node (ref "PWML") (pin "4") (pinfunction "4_4") (pintype "passive"))
      (node (ref "U1") (pin "139") (pinfunction "PC28_139") (pintype "passive"))
    )
    (net (code "105") (name "/PWM5") (class "Default")
      (node (ref "PWML") (pin "6") (pinfunction "6_6") (pintype "passive"))
      (node (ref "U1") (pin "136") (pinfunction "PC25_136") (pintype "passive"))
    )
    (net (code "106") (name "/PWM6") (class "Default")
      (node (ref "PWML") (pin "7") (pinfunction "7_7") (pintype "passive"))
      (node (ref "U1") (pin "135") (pinfunction "PC24_135") (pintype "passive"))
    )
    (net (code "107") (name "/PWM7") (class "Default")
      (node (ref "PWML") (pin "8") (pinfunction "8_8") (pintype "passive"))
      (node (ref "U1") (pin "134") (pinfunction "PC23_134") (pintype "passive"))
    )
    (net (code "108") (name "/PWM8") (class "Default")
      (node (ref "PWMH") (pin "1") (pinfunction "1_1") (pintype "passive"))
      (node (ref "U1") (pin "133") (pinfunction "PC22_133") (pintype "passive"))
    )
    (net (code "109") (name "/PWM9") (class "Default")
      (node (ref "PWMH") (pin "2") (pinfunction "2_2") (pintype "passive"))
      (node (ref "U1") (pin "132") (pinfunction "PC21_132") (pintype "passive"))
    )
    (net (code "110") (name "/PWM11") (class "Default")
      (node (ref "PWMH") (pin "4") (pinfunction "4_4") (pintype "passive"))
      (node (ref "U1") (pin "20") (pinfunction "PD7_20") (pintype "passive"))
    )
    (net (code "111") (name "/PWM12") (class "Default")
      (node (ref "PWMH") (pin "5") (pinfunction "5_5") (pintype "passive"))
      (node (ref "U1") (pin "21") (pinfunction "PD8_21") (pintype "passive"))
    )
    (net (code "112") (name "/PWM13") (class "Default")
      (node (ref "IC1") (pin "3") (pinfunction "+IN_3") (pintype "passive"))
      (node (ref "PWMH") (pin "6") (pinfunction "6_6") (pintype "passive"))
      (node (ref "U1") (pin "68") (pinfunction "PB27_68") (pintype "passive"))
    )
    (net (code "113") (name "/RD+") (class "Default")
      (node (ref "IC6") (pin "29") (pinfunction "D+_29") (pintype "passive"))
      (node (ref "R20") (pin "1") (pinfunction "1_1") (pintype "passive"))
    )
    (net (code "114") (name "/RD-") (class "Default")
      (node (ref "IC6") (pin "30") (pinfunction "D-_30") (pintype "passive"))
      (node (ref "R19") (pin "1") (pinfunction "1_1") (pintype "passive"))
    )
    (net (code "115") (name "/RESET2") (class "Default")
      (node (ref "D2") (pin "A") (pinfunction "A_A") (pintype "passive"))
      (node (ref "IC6") (pin "24") (pinfunction "RESET(PC1/DW)_24") (pintype "passive"))
      (node (ref "ICSP1") (pin "5") (pinfunction "5_5") (pintype "passive"))
      (node (ref "R13") (pin "1") (pinfunction "1_1") (pintype "passive"))
    )
    (net (code "116") (name "/RESETA") (class "Default")
      (node (ref "MACB") (pin "2") (pinfunction "2_2") (pintype "passive+no_connect"))
    )
    (net (code "117") (name "/RESET_CMD") (class "Default")
      (node (ref "IC6") (pin "22") (pinfunction "(INT4/ICP1/CLK0)PC7_22") (pintype "passive"))
      (node (ref "R23") (pin "1") (pinfunction "1_1") (pintype "passive"))
    )
    (net (code "118") (name "/RX") (class "Default")
      (node (ref "IC10") (pin "4") (pinfunction "O_4") (pintype "passive"))
      (node (ref "PWML") (pin "1") (pinfunction "1_1") (pintype "passive"))
      (node (ref "U1") (pin "27") (pinfunction "PA8_27") (pintype "passive"))
    )
    (net (code "119") (name "/RXD0") (class "Default")
      (node (ref "COMMUNICATION") (pin "2") (pinfunction "2_2") (pintype "passive"))
      (node (ref "U1") (pin "18") (pinfunction "PD5_18") (pintype "passive"))
    )
    (net (code "120") (name "/RXD1") (class "Default")
      (node (ref "COMMUNICATION") (pin "4") (pinfunction "4_4") (pintype "passive"))
      (node (ref "U1") (pin "5") (pinfunction "PA12_5") (pintype "passive"))
    )
    (net (code "121") (name "/RXD2") (class "Default")
      (node (ref "COMMUNICATION") (pin "6") (pinfunction "6_6") (pintype "passive"))
      (node (ref "U1") (pin "3") (pinfunction "PA10_3") (pintype "passive"))
    )
    (net (code "122") (name "/RXL") (class "Default")
      (node (ref "RX") (pin "C") (pinfunction "C_C") (pintype "passive"))
      (node (ref "U1") (pin "103") (pinfunction "PC30_103") (pintype "passive"))
    )
    (net (code "123") (name "/RXL-U2") (class "Default")
      (node (ref "IC6") (pin "10") (pinfunction "(INT5/AIN3)PD4_10") (pintype "passive"))
      (node (ref "RX1") (pin "C") (pinfunction "C_C") (pintype "passive"))
    )
    (net (code "124") (name "/SCK2") (class "Default")
      (node (ref "IC6") (pin "15") (pinfunction "(SCLK/PCINT1)PB1_15") (pintype "passive"))
      (node (ref "ICSP1") (pin "3") (pinfunction "3_3") (pintype "passive"))
    )
    (net (code "125") (name "/SCL0-3") (class "Default")
      (node (ref "COMMUNICATION") (pin "8") (pinfunction "8_8") (pintype "passive"))
      (node (ref "RN5") (pin "7") (pinfunction "2_7") (pintype "passive"))
      (node (ref "U1") (pin "87") (pinfunction "PB13_87") (pintype "passive"))
    )
    (net (code "126") (name "/SCL1") (class "Default")
      (node (ref "PWMH") (pin "10") (pinfunction "10_10") (pintype "passive"))
      (node (ref "U1") (pin "70") (pinfunction "PA18_70") (pintype "passive"))
    )
    (net (code "127") (name "/SDA0-3") (class "Default")
      (node (ref "COMMUNICATION") (pin "7") (pinfunction "7_7") (pintype "passive"))
      (node (ref "RN5") (pin "8") (pinfunction "2_8") (pintype "passive"))
      (node (ref "U1") (pin "86") (pinfunction "PB12_86") (pintype "passive"))
    )
    (net (code "128") (name "/SDA1") (class "Default")
      (node (ref "PWMH") (pin "9") (pinfunction "9_9") (pintype "passive"))
      (node (ref "U1") (pin "9") (pinfunction "PA17_9") (pintype "passive"))
    )
    (net (code "129") (name "/SPCK") (class "Default")
      (node (ref "SPI") (pin "3") (pinfunction "3_3") (pintype "passive"))
      (node (ref "U1") (pin "110") (pinfunction "PA27_110") (pintype "passive"))
    )
    (net (code "130") (name "/SS0{slash}PWM10") (class "Default")
      (node (ref "PWMH") (pin "3") (pinfunction "3_3") (pintype "passive"))
      (node (ref "U1") (pin "102") (pinfunction "PC29_102") (pintype "passive"))
      (node (ref "U1") (pin "111") (pinfunction "PA28_111") (pintype "passive"))
    )
    (net (code "131") (name "/SS1{slash}PWM4") (class "Default")
      (node (ref "PWML") (pin "5") (pinfunction "5_5") (pintype "passive"))
      (node (ref "U1") (pin "112") (pinfunction "PA29_112") (pintype "passive"))
      (node (ref "U1") (pin "137") (pinfunction "PC26_137") (pintype "passive"))
    )
    (net (code "132") (name "/SS3") (class "Default")
      (node (ref "U1") (pin "142") (pinfunction "PB23_142") (pintype "passive"))
    )
    (net (code "133") (name "/SW") (class "Default")
      (node (ref "C42") (pin "2") (pinfunction "2_2") (pintype "passive"))
      (node (ref "D4") (pin "P$1") (pinfunction "K_P$1") (pintype "passive"))
      (node (ref "IC2") (pin "6") (pinfunction "SW_6") (pintype "passive"))
      (node (ref "L4") (pin "P$1") (pinfunction "1_P$1") (pintype "passive"))
    )
    (net (code "134") (name "/TX") (class "Default")
      (node (ref "IC6") (pin "8") (pinfunction "(RXD1/AIN1/INT2)PD2_8") (pintype "passive"))
      (node (ref "PWML") (pin "2") (pinfunction "2_2") (pintype "passive"))
      (node (ref "U1") (pin "2") (pinfunction "PA9_2") (pintype "passive"))
    )
    (net (code "135") (name "/TXD0") (class "Default")
      (node (ref "COMMUNICATION") (pin "1") (pinfunction "1_1") (pintype "passive"))
      (node (ref "U1") (pin "17") (pinfunction "PD4_17") (pintype "passive"))
    )
    (net (code "136") (name "/TXD1") (class "Default")
      (node (ref "COMMUNICATION") (pin "3") (pinfunction "3_3") (pintype "passive"))
      (node (ref "U1") (pin "6") (pinfunction "PA13_6") (pintype "passive"))
    )
    (net (code "137") (name "/TXD2") (class "Default")
      (node (ref "COMMUNICATION") (pin "5") (pinfunction "5_5") (pintype "passive"))
      (node (ref "U1") (pin "4") (pinfunction "PA11_4") (pintype "passive"))
    )
    (net (code "138") (name "/TXL") (class "Default")
      (node (ref "TX") (pin "C") (pinfunction "C_C") (pintype "passive"))
      (node (ref "U1") (pin "107") (pinfunction "PA21_107") (pintype "passive"))
    )
    (net (code "139") (name "/TXL-U2") (class "Default")
      (node (ref "IC6") (pin "11") (pinfunction "(XCK/AIN4/PCINT12)PD5_11") (pintype "passive"))
      (node (ref "TX1") (pin "C") (pinfunction "C_C") (pintype "passive"))
    )
    (net (code "140") (name "/UOTGID") (class "Default")
      (node (ref "U1") (pin "129") (pinfunction "PB11_129") (pintype "passive"))
      (node (ref "USB1") (pin "4") (pinfunction "ID_4") (pintype "passive"))
      (node (ref "Z5") (pin "2") (pinfunction "2_2") (pintype "passive"))
    )
    (net (code "141") (name "/UOTGVBOF") (class "Default")
      (node (ref "R3") (pin "1") (pinfunction "1_1") (pintype "passive"))
      (node (ref "U1") (pin "128") (pinfunction "PB10_128") (pintype "passive"))
    )
    (net (code "142") (name "/USBVCC") (class "Default")
      (node (ref "C27") (pin "+") (pinfunction "+_+") (pintype "passive"))
      (node (ref "C35") (pin "+") (pinfunction "+_+") (pintype "passive"))
      (node (ref "F1") (pin "1") (pinfunction "1_1") (pintype "passive"))
      (node (ref "R2") (pin "2") (pinfunction "2_2") (pintype "passive"))
      (node (ref "R21") (pin "2") (pinfunction "2_2") (pintype "passive"))
      (node (ref "T1") (pin "1") (pinfunction "D_1") (pintype "passive"))
    )
    (net (code "143") (name "/USBVCCU2") (class "Default")
      (node (ref "C28") (pin "1") (pinfunction "1_1") (pintype "passive"))
      (node (ref "F2") (pin "1") (pinfunction "1_1") (pintype "passive"))
      (node (ref "IC6") (pin "31") (pinfunction "UVCC_31") (pintype "passive"))
      (node (ref "T2") (pin "1") (pinfunction "D_1") (pintype "passive"))
    )
    (net (code "144") (name "/VBG") (class "Default")
      (node (ref "C25") (pin "1") (pinfunction "1_1") (pintype "passive"))
      (node (ref "R7") (pin "2") (pinfunction "2_2") (pintype "passive"))
      (node (ref "U1") (pin "40") (pinfunction "VBG_40") (pintype "passive"))
    )
    (net (code "145") (name "/VDDANA") (class "Default")
      (node (ref "C10") (pin "2") (pinfunction "2_2") (pintype "passive"))
      (node (ref "C3") (pin "+") (pinfunction "+_+") (pintype "passive"))
      (node (ref "L1") (pin "2") (pinfunction "2_2") (pintype "passive"))
      (node (ref "U1") (pin "73") (pinfunction "VDDANA_73") (pintype "passive"))
    )
    (net (code "146") (name "/VDDOUT") (class "Default")
      (node (ref "C11") (pin "+") (pinfunction "+_+") (pintype "passive"))
      (node (ref "C12") (pin "2") (pinfunction "2_2") (pintype "passive"))
      (node (ref "C13") (pin "2") (pinfunction "2_2") (pintype "passive"))
      (node (ref "C14") (pin "2") (pinfunction "2_2") (pintype "passive"))
      (node (ref "C15") (pin "2") (pinfunction "2_2") (pintype "passive"))
      (node (ref "C16") (pin "2") (pinfunction "2_2") (pintype "passive"))
      (node (ref "C17") (pin "2") (pinfunction "2_2") (pintype "passive"))
      (node (ref "L5") (pin "1") (pinfunction "1_1") (pintype "passive"))
      (node (ref "U1") (pin "10") (pinfunction "VDDCORE1_10") (pintype "passive"))
      (node (ref "U1") (pin "104") (pinfunction "VDDCORE4_104") (pintype "passive"))
      (node (ref "U1") (pin "124") (pinfunction "VDDCORE5_124") (pintype "passive"))
      (node (ref "U1") (pin "45") (pinfunction "VDDCORE2_45") (pintype "passive"))
      (node (ref "U1") (pin "56") (pinfunction "VDDOUT_56") (pintype "passive"))
      (node (ref "U1") (pin "61") (pinfunction "VDDCORE3_61") (pintype "passive"))
    )
    (net (code "147") (name "/VDDOUTMI") (class "Default")
      (node (ref "C2") (pin "+") (pinfunction "+_+") (pintype "passive"))
      (node (ref "C9") (pin "2") (pinfunction "2_2") (pintype "passive"))
      (node (ref "L2") (pin "2") (pinfunction "2_2") (pintype "passive"))
      (node (ref "U1") (pin "41") (pinfunction "VDDUTMI_41") (pintype "passive"))
    )
    (net (code "148") (name "/VDDPLL") (class "Default")
      (node (ref "C32") (pin "2") (pinfunction "2_2") (pintype "passive"))
      (node (ref "C33") (pin "+") (pinfunction "+_+") (pintype "passive"))
      (node (ref "L5") (pin "2") (pinfunction "2_2") (pintype "passive"))
      (node (ref "U1") (pin "34") (pinfunction "VDDPLL_34") (pintype "passive"))
    )
    (net (code "149") (name "/VIN") (class "Default")
      (node (ref "C41") (pin "+") (pinfunction "+_+") (pintype "passive"))
      (node (ref "IC2") (pin "5") (pinfunction "VIN_5") (pintype "passive"))
      (node (ref "L6") (pin "1") (pinfunction "1_1") (pintype "passive"))
      (node (ref "PC1") (pin "+") (pinfunction "+_+") (pintype "passive"))
      (node (ref "POWER") (pin "8") (pinfunction "8_8") (pintype "passive"))
      (node (ref "R10") (pin "1") (pinfunction "1_1") (pintype "passive"))
      (node (ref "RN4") (pin "6") (pinfunction "2_6") (pintype "passive"))
    )
    (net (code "150") (name "/VIN+") (class "Default")
      (node (ref "D1") (pin "C") (pinfunction "C_C") (pintype "passive"))
      (node (ref "L6") (pin "2") (pinfunction "2_2") (pintype "passive"))
      (node (ref "X2") (pin "2") (pinfunction "2_2") (pintype "passive"))
    )
    (net (code "151") (name "/VUCAP") (class "Default")
      (node (ref "C38") (pin "1") (pinfunction "1_1") (pintype "passive"))
      (node (ref "IC6") (pin "27") (pinfunction "UCAP_27") (pintype "passive"))
    )
    (net (code "152") (name "/XIN") (class "Default")
      (node (ref "C22") (pin "1") (pinfunction "1_1") (pintype "passive"))
      (node (ref "U1") (pin "36") (pinfunction "XIN_36") (pintype "passive"))
      (node (ref "Y1") (pin "1") (pinfunction "C1_1") (pintype "passive"))
    )
    (net (code "153") (name "/XIN32") (class "Default")
      (node (ref "C24") (pin "1") (pinfunction "1_1") (pintype "passive"))
      (node (ref "U1") (pin "48") (pinfunction "XIN32_48") (pintype "passive"))
      (node (ref "Y2") (pin "P$2") (pinfunction "2_P$2") (pintype "passive"))
    )
    (net (code "154") (name "/XOUT") (class "Default")
      (node (ref "C21") (pin "1") (pinfunction "1_1") (pintype "passive"))
      (node (ref "U1") (pin "35") (pinfunction "XOUT_35") (pintype "passive"))
      (node (ref "Y1") (pin "3") (pinfunction "C2_3") (pintype "passive"))
    )
    (net (code "155") (name "/XOUT32") (class "Default")
      (node (ref "C23") (pin "1") (pinfunction "1_1") (pintype "passive"))
      (node (ref "U1") (pin "49") (pinfunction "XOUT32_49") (pintype "passive"))
      (node (ref "Y2") (pin "P$1") (pinfunction "1_P$1") (pintype "passive"))
    )
    (net (code "156") (name "/XT1") (class "Default")
      (node (ref "C39") (pin "1") (pinfunction "1_1") (pintype "passive"))
      (node (ref "IC6") (pin "1") (pinfunction "XTAL1_1") (pintype "passive"))
      (node (ref "R9") (pin "1") (pinfunction "1_1") (pintype "passive"))
      (node (ref "Y4") (pin "1") (pinfunction "C1_1") (pintype "passive"))
    )
    (net (code "157") (name "/XT2") (class "Default")
      (node (ref "C40") (pin "1") (pinfunction "1_1") (pintype "passive"))
      (node (ref "IC6") (pin "2") (pinfunction "XTAL2(PC0)_2") (pintype "passive"))
      (node (ref "R9") (pin "2") (pinfunction "2_2") (pintype "passive"))
      (node (ref "Y4") (pin "3") (pinfunction "C2_3") (pintype "passive"))
    )
    (net (code "158") (name "/XUSB") (class "Default")
      (node (ref "C26") (pin "1") (pinfunction "1_1") (pintype "passive"))
      (node (ref "F1") (pin "2") (pinfunction "2_2") (pintype "passive"))
      (node (ref "U1") (pin "39") (pinfunction "VBUS_39") (pintype "passive"))
      (node (ref "USB1") (pin "1") (pinfunction "VUSB_1") (pintype "passive"))
    )
    (net (code "159") (name "/XVCC") (class "Default")
      (node (ref "F2") (pin "2") (pinfunction "2_2") (pintype "passive"))
      (node (ref "J3") (pin "P1") (pinfunction "VBUS_P1") (pintype "passive"))
    )
    (net (code "160") (name "GND") (class "Default")
      (node (ref "C1") (pin "-") (pinfunction "-_-") (pintype "passive"))
      (node (ref "C10") (pin "1") (pinfunction "1_1") (pintype "passive"))
      (node (ref "C11") (pin "-") (pinfunction "-_-") (pintype "passive"))
      (node (ref "C12") (pin "1") (pinfunction "1_1") (pintype "passive"))
      (node (ref "C13") (pin "1") (pinfunction "1_1") (pintype "passive"))
      (node (ref "C14") (pin "1") (pinfunction "1_1") (pintype "passive"))
      (node (ref "C15") (pin "1") (pinfunction "1_1") (pintype "passive"))
      (node (ref "C16") (pin "1") (pinfunction "1_1") (pintype "passive"))
      (node (ref "C17") (pin "1") (pinfunction "1_1") (pintype "passive"))
      (node (ref "C18") (pin "1") (pinfunction "1_1") (pintype "passive"))
      (node (ref "C19") (pin "1") (pinfunction "1_1") (pintype "passive"))
      (node (ref "C2") (pin "-") (pinfunction "-_-") (pintype "passive"))
      (node (ref "C21") (pin "2") (pinfunction "2_2") (pintype "passive"))
      (node (ref "C22") (pin "2") (pinfunction "2_2") (pintype "passive"))
      (node (ref "C23") (pin "2") (pinfunction "2_2") (pintype "passive"))
      (node (ref "C24") (pin "2") (pinfunction "2_2") (pintype "passive"))
      (node (ref "C25") (pin "2") (pinfunction "2_2") (pintype "passive"))
      (node (ref "C26") (pin "2") (pinfunction "2_2") (pintype "passive"))
      (node (ref "C27") (pin "-") (pinfunction "-_-") (pintype "passive"))
      (node (ref "C28") (pin "2") (pinfunction "2_2") (pintype "passive"))
      (node (ref "C29") (pin "-") (pinfunction "-_-") (pintype "passive"))
      (node (ref "C3") (pin "-") (pinfunction "-_-") (pintype "passive"))
      (node (ref "C30") (pin "1") (pinfunction "1_1") (pintype "passive"))
      (node (ref "C31") (pin "1") (pinfunction "1_1") (pintype "passive"))
      (node (ref "C32") (pin "1") (pinfunction "1_1") (pintype "passive"))
      (node (ref "C33") (pin "-") (pinfunction "-_-") (pintype "passive"))
      (node (ref "C34") (pin "1") (pinfunction "1_1") (pintype "passive"))
      (node (ref "C35") (pin "-") (pinfunction "-_-") (pintype "passive"))
      (node (ref "C36") (pin "2") (pinfunction "2_2") (pintype "passive"))
      (node (ref "C37") (pin "2") (pinfunction "2_2") (pintype "passive"))
      (node (ref "C38") (pin "2") (pinfunction "2_2") (pintype "passive"))
      (node (ref "C39") (pin "2") (pinfunction "2_2") (pintype "passive"))
      (node (ref "C4") (pin "1") (pinfunction "1_1") (pintype "passive"))
      (node (ref "C40") (pin "2") (pinfunction "2_2") (pintype "passive"))
      (node (ref "C41") (pin "-") (pinfunction "-_-") (pintype "passive"))
      (node (ref "C5") (pin "1") (pinfunction "1_1") (pintype "passive"))
      (node (ref "C6") (pin "1") (pinfunction "1_1") (pintype "passive"))
      (node (ref "C7") (pin "1") (pinfunction "1_1") (pintype "passive"))
      (node (ref "C8") (pin "1") (pinfunction "1_1") (pintype "passive"))
      (node (ref "C9") (pin "1") (pinfunction "1_1") (pintype "passive"))
      (node (ref "D1") (pin "A") (pinfunction "A_A") (pintype "passive"))
      (node (ref "D4") (pin "P$2") (pinfunction "A_P$2") (pintype "passive"))
      (node (ref "DEBUG") (pin "1") (pinfunction "1_1") (pintype "passive"))
      (node (ref "IC1") (pin "4") (pinfunction "V-_4") (pintype "passive"))
      (node (ref "IC10") (pin "1") (pinfunction "OE_1") (pintype "passive"))
      (node (ref "IC10") (pin "3") (pinfunction "GND_3") (pintype "passive"))
      (node (ref "IC2") (pin "2") (pinfunction "GND_2") (pintype "passive"))
      (node (ref "IC4") (pin "1") (pinfunction "GND/ADJ_1") (pintype "passive"))
      (node (ref "IC6") (pin "28") (pinfunction "UGND_28") (pintype "passive"))
      (node (ref "IC6") (pin "3") (pinfunction "GND_3") (pintype "passive"))
      (node (ref "IC6") (pin "33") (pinfunction "PAD_33") (pintype "passive"))
      (node (ref "ICSP1") (pin "6") (pinfunction "6_6") (pintype "passive"))
      (node (ref "J3") (pin "P$1") (pinfunction "SH7_P$1") (pintype "passive"))
      (node (ref "J3") (pin "P$2") (pinfunction "SH8_P$2") (pintype "passive"))
      (node (ref "J3") (pin "P$3") (pinfunction "SH9_P$3") (pintype "passive"))
      (node (ref "J3") (pin "P$4") (pinfunction "SH10_P$4") (pintype "passive"))
      (node (ref "J3") (pin "P$5") (pinfunction "SH11_P$5") (pintype "passive"))
      (node (ref "J3") (pin "P$6") (pinfunction "SH12_P$6") (pintype "passive"))
      (node (ref "J3") (pin "P$7") (pinfunction "SH13_P$7") (pintype "passive"))
      (node (ref "J3") (pin "P$8") (pinfunction "SH14_P$8") (pintype "passive"))
      (node (ref "J3") (pin "P5") (pinfunction "GND_P5") (pintype "passive"))
      (node (ref "J3") (pin "S1") (pinfunction "SH1_S1") (pintype "passive"))
      (node (ref "J3") (pin "S2") (pinfunction "SH2_S2") (pintype "passive"))
      (node (ref "J3") (pin "S3") (pinfunction "SH3_S3") (pintype "passive"))
      (node (ref "J3") (pin "S4") (pinfunction "SH4_S4") (pintype "passive"))
      (node (ref "J3") (pin "S5") (pinfunction "SH5_S5") (pintype "passive"))
      (node (ref "J3") (pin "S6") (pinfunction "SH6_S6") (pintype "passive"))
      (node (ref "JTAG") (pin "3") (pinfunction "3_3") (pintype "passive"))
      (node (ref "JTAG") (pin "5") (pinfunction "5_5") (pintype "passive"))
      (node (ref "JTAG") (pin "9") (pinfunction "9_9") (pintype "passive"))
      (node (ref "L") (pin "C") (pinfunction "C_C") (pintype "passive"))
      (node (ref "ON") (pin "C") (pinfunction "C_C") (pintype "passive"))
      (node (ref "PC1") (pin "-") (pinfunction "-_-") (pintype "passive"))
      (node (ref "PC2") (pin "-") (pinfunction "-_-") (pintype "passive"))
      (node (ref "POWER") (pin "6") (pinfunction "6_6") (pintype "passive"))
      (node (ref "POWER") (pin "7") (pinfunction "7_7") (pintype "passive"))
      (node (ref "PWMH") (pin "7") (pinfunction "7_7") (pintype "passive"))
      (node (ref "Q2") (pin "2") (pinfunction "E_2") (pintype "passive"))
      (node (ref "R11") (pin "2") (pinfunction "2_2") (pintype "passive"))
      (node (ref "R18") (pin "2") (pinfunction "2_2") (pintype "passive"))
      (node (ref "R2") (pin "1") (pinfunction "1_1") (pintype "passive"))
      (node (ref "R7") (pin "1") (pinfunction "1_1") (pintype "passive"))
      (node (ref "R8") (pin "1") (pinfunction "1_1") (pintype "passive"))
      (node (ref "RESET") (pin "1") (pinfunction "1_1") (pintype "passive"))
      (node (ref "RESET") (pin "2") (pinfunction "2_2") (pintype "passive"))
      (node (ref "RN1") (pin "1") (pinfunction "1_1") (pintype "passive"))
      (node (ref "RN1") (pin "2") (pinfunction "1_2") (pintype "passive"))
      (node (ref "RN1") (pin "7") (pinfunction "2_7") (pintype "passive"))
      (node (ref "RN1") (pin "8") (pinfunction "2_8") (pintype "passive"))
      (node (ref "RN2") (pin "1") (pinfunction "1_1") (pintype "passive"))
      (node (ref "RN2") (pin "4") (pinfunction "1_4") (pintype "passive"))
      (node (ref "RN2") (pin "5") (pinfunction "2_5") (pintype "passive"))
      (node (ref "RN2") (pin "8") (pinfunction "2_8") (pintype "passive"))
      (node (ref "RN4") (pin "1") (pinfunction "1_1") (pintype "passive"))
      (node (ref "RN4") (pin "2") (pinfunction "1_2") (pintype "passive"))
      (node (ref "RN4") (pin "5") (pinfunction "2_5") (pintype "passive"))
      (node (ref "RN4") (pin "7") (pinfunction "2_7") (pintype "passive"))
      (node (ref "SPI") (pin "6") (pinfunction "6_6") (pintype "passive"))
      (node (ref "T2") (pin "3") (pinfunction "G_3") (pintype "passive"))
      (node (ref "U1") (pin "106") (pinfunction "GND3_106") (pintype "passive"))
      (node (ref "U1") (pin "12") (pinfunction "GND1_12") (pintype "passive"))
      (node (ref "U1") (pin "126") (pinfunction "GND4_126") (pintype "passive"))
      (node (ref "U1") (pin "33") (pinfunction "GNDPLL_33") (pintype "passive"))
      (node (ref "U1") (pin "44") (pinfunction "GNDUTMI_44") (pintype "passive"))
      (node (ref "U1") (pin "46") (pinfunction "JTAGSEL_46") (pintype "passive"))
      (node (ref "U1") (pin "54") (pinfunction "GNDBU_54") (pintype "passive"))
      (node (ref "U1") (pin "58") (pinfunction "GND2_58") (pintype "passive"))
      (node (ref "U1") (pin "74") (pinfunction "GNDANA_74") (pintype "passive"))
      (node (ref "USB1") (pin "5") (pinfunction "UGND_5") (pintype "passive"))
      (node (ref "USB1") (pin "P$1") (pinfunction "G1_P$1") (pintype "passive"))
      (node (ref "USB1") (pin "P$10") (pinfunction "G10_P$10") (pintype "passive"))
      (node (ref "USB1") (pin "P$11") (pinfunction "G11_P$11") (pintype "passive"))
      (node (ref "USB1") (pin "P$2") (pinfunction "G2_P$2") (pintype "passive"))
      (node (ref "USB1") (pin "P$3") (pinfunction "G3_P$3") (pintype "passive"))
      (node (ref "USB1") (pin "P$4") (pinfunction "G4_P$4") (pintype "passive"))
      (node (ref "USB1") (pin "P$5") (pinfunction "G5_P$5") (pintype "passive"))
      (node (ref "USB1") (pin "P$6") (pinfunction "G6_P$6") (pintype "passive"))
      (node (ref "USB1") (pin "P$7") (pinfunction "G7_P$7") (pintype "passive"))
      (node (ref "USB1") (pin "P$8") (pinfunction "G8_P$8") (pintype "passive"))
      (node (ref "USB1") (pin "P$9") (pinfunction "G9_P$9") (pintype "passive"))
      (node (ref "USB1") (pin "S1") (pinfunction "SH1_S1") (pintype "passive"))
      (node (ref "USB1") (pin "S2") (pinfunction "SH2_S2") (pintype "passive"))
      (node (ref "USB1") (pin "S3") (pinfunction "SH3_S3") (pintype "passive"))
      (node (ref "USB1") (pin "S4") (pinfunction "SH4_S4") (pintype "passive"))
      (node (ref "X2") (pin "1") (pinfunction "1_1") (pintype "passive"))
      (node (ref "X2") (pin "3") (pinfunction "3_3") (pintype "passive"))
      (node (ref "XIO") (pin "35") (pinfunction "35_35") (pintype "passive"))
      (node (ref "XIO") (pin "36") (pinfunction "36_36") (pintype "passive"))
      (node (ref "Y1") (pin "2") (pinfunction "GND@1_2") (pintype "passive"))
      (node (ref "Y1") (pin "4") (pinfunction "GND@2_4") (pintype "passive"))
      (node (ref "Y4") (pin "2") (pinfunction "GND@1_2") (pintype "passive"))
      (node (ref "Y4") (pin "4") (pinfunction "GND@2_4") (pintype "passive"))
      (node (ref "Z1") (pin "2") (pinfunction "2_2") (pintype "passive"))
      (node (ref "Z2") (pin "2") (pinfunction "2_2") (pintype "passive"))
      (node (ref "Z3") (pin "1") (pinfunction "1_1") (pintype "passive"))
      (node (ref "Z4") (pin "1") (pinfunction "1_1") (pintype "passive"))
      (node (ref "Z5") (pin "1") (pinfunction "1_1") (pintype "passive"))
    )
    (net (code "161") (name "Net-(BR1-C)") (class "Default")
      (node (ref "BR1") (pin "2") (pinfunction "C_2") (pintype "passive"))
      (node (ref "C34") (pin "2") (pinfunction "2_2") (pintype "passive"))
      (node (ref "JR1") (pin "2") (pinfunction "2_2") (pintype "passive"))
      (node (ref "L3") (pin "1") (pinfunction "1_1") (pintype "passive"))
    )
    (net (code "162") (name "Net-(IC6-(CTS{slash}HWB{slash}AIN6{slash}TO{slash}INT7)PD7)") (class "Default")
      (node (ref "IC6") (pin "13") (pinfunction "(CTS/HWB/AIN6/TO/INT7)PD7_13") (pintype "passive"))
      (node (ref "R18") (pin "1") (pinfunction "1_1") (pintype "passive"))
    )
    (net (code "163") (name "Net-(POWER-Pad1)") (class "Default")
      (node (ref "POWER") (pin "1") (pinfunction "1_1") (pintype "passive"))
    )
    (net (code "164") (name "Net-(Q2-B)") (class "Default")
      (node (ref "Q2") (pin "1") (pinfunction "B_1") (pintype "passive"))
      (node (ref "R3") (pin "2") (pinfunction "2_2") (pintype "passive"))
      (node (ref "RN4") (pin "8") (pinfunction "2_8") (pintype "passive"))
    )
    (net (code "165") (name "Net-(R14-Pad2)") (class "Default")
      (node (ref "R14") (pin "2") (pinfunction "2_2") (pintype "passive"))
      (node (ref "TX1") (pin "A") (pinfunction "A_A") (pintype "passive"))
    )
    (net (code "166") (name "Net-(R15-Pad2)") (class "Default")
      (node (ref "R15") (pin "2") (pinfunction "2_2") (pintype "passive"))
      (node (ref "RX1") (pin "A") (pinfunction "A_A") (pintype "passive"))
    )
    (net (code "167") (name "Net-(RN3-Pad1)") (class "Default")
      (node (ref "RN3") (pin "1") (pinfunction "1_1") (pintype "passive"))
      (node (ref "RX") (pin "A") (pinfunction "A_A") (pintype "passive"))
    )
    (net (code "168") (name "Net-(RN3B-1)") (class "Default")
      (node (ref "RN3") (pin "2") (pinfunction "1_2") (pintype "passive"))
      (node (ref "TX") (pin "A") (pinfunction "A_A") (pintype "passive"))
    )
    (net (code "169") (name "Net-(RN3C-1)") (class "Default")
      (node (ref "L") (pin "A") (pinfunction "A_A") (pintype "passive"))
      (node (ref "RN3") (pin "3") (pinfunction "1_3") (pintype "passive"))
    )
    (net (code "170") (name "Net-(RN3D-1)") (class "Default")
      (node (ref "ON") (pin "A") (pinfunction "A_A") (pintype "passive"))
      (node (ref "RN3") (pin "4") (pinfunction "1_4") (pintype "passive"))
    )
    (net (code "171") (name "Net-(U1-DFSDM)") (class "Default")
      (node (ref "R5") (pin "2") (pinfunction "2_2") (pintype "passive"))
      (node (ref "U1") (pin "43") (pinfunction "DFSDM_43") (pintype "passive"))
    )
    (net (code "172") (name "Net-(U1-DFSDP)") (class "Default")
      (node (ref "R6") (pin "2") (pinfunction "2_2") (pintype "passive"))
      (node (ref "U1") (pin "42") (pinfunction "DFSDP_42") (pintype "passive"))
    )
    (net (code "173") (name "Net-(U1-FWUP)") (class "Default")
      (node (ref "R4") (pin "1") (pinfunction "1_1") (pintype "passive"))
      (node (ref "U1") (pin "53") (pinfunction "FWUP_53") (pintype "passive"))
    )
    (net (code "174") (name "Net-(U1-TST)") (class "Default")
      (node (ref "R8") (pin "2") (pinfunction "2_2") (pintype "passive"))
      (node (ref "U1") (pin "51") (pinfunction "TST_51") (pintype "passive"))
    )
    (net (code "175") (name "unconnected-(IC6-(AIN0{slash}INT1)PD1-Pad7)") (class "Default")
      (node (ref "IC6") (pin "7") (pinfunction "(AIN0/INT1)PD1_7") (pintype "passive+no_connect"))
    )
    (net (code "176") (name "unconnected-(IC6-(AIN2{slash}PCINT11)PC2-Pad5)") (class "Default")
      (node (ref "IC6") (pin "5") (pinfunction "(AIN2/PCINT11)PC2_5") (pintype "passive+no_connect"))
    )
    (net (code "177") (name "unconnected-(IC6-(OC0B{slash}INT0)PD0-Pad6)") (class "Default")
      (node (ref "IC6") (pin "6") (pinfunction "(OC0B/INT0)PD0_6") (pintype "passive+no_connect"))
    )
    (net (code "178") (name "unconnected-(IC6-(PCINT9{slash}OC1B)PC5-Pad25)") (class "Default")
      (node (ref "IC6") (pin "25") (pinfunction "(PCINT9/OC1B)PC5_25") (pintype "passive"))
    )
    (net (code "179") (name "unconnected-(IC6-(RTS{slash}AIN5{slash}INT6)PD6-Pad12)") (class "Default")
      (node (ref "IC6") (pin "12") (pinfunction "(RTS/AIN5/INT6)PD6_12") (pintype "passive+no_connect"))
    )
    (net (code "180") (name "unconnected-(IC6-(SS{slash}PCINT0)PB0-Pad14)") (class "Default")
      (node (ref "IC6") (pin "14") (pinfunction "(SS/PCINT0)PB0_14") (pintype "passive+no_connect"))
    )
    (net (code "181") (name "unconnected-(J3-ID-PadP4)") (class "Default")
      (node (ref "J3") (pin "P4") (pinfunction "ID_P4") (pintype "passive+no_connect"))
    )
    (net (code "182") (name "unconnected-(JTAG-Pad7)") (class "Default")
      (node (ref "JTAG") (pin "7") (pinfunction "7_7") (pintype "passive+no_connect"))
    )
    (net (code "183") (name "unconnected-(MACB-Pad4)") (class "Default")
      (node (ref "MACB") (pin "4") (pinfunction "4_4") (pintype "passive+no_connect"))
    )
    (net (code "184") (name "unconnected-(MACB-Pad6)") (class "Default")
      (node (ref "MACB") (pin "6") (pinfunction "6_6") (pintype "passive+no_connect"))
    )
    (net (code "185") (name "unconnected-(RESET-5-GND-Pad5)") (class "Default")
      (node (ref "RESET") (pin "5") (pinfunction "5-GND_5") (pintype "passive+no_connect"))
    )
    (net (code "186") (name "unconnected-(RN5C-1-Pad3)") (class "Default")
      (node (ref "RN5") (pin "3") (pinfunction "1_3") (pintype "passive+no_connect"))
    )
    (net (code "187") (name "unconnected-(RN5C-2-Pad6)") (class "Default")
      (node (ref "RN5") (pin "6") (pinfunction "2_6") (pintype "passive+no_connect"))
    )
    (net (code "188") (name "unconnected-(RN5D-1-Pad4)") (class "Default")
      (node (ref "RN5") (pin "4") (pinfunction "1_4") (pintype "passive+no_connect"))
    )
    (net (code "189") (name "unconnected-(RN5D-2-Pad5)") (class "Default")
      (node (ref "RN5") (pin "5") (pinfunction "2_5") (pintype "passive+no_connect"))
    )
    (net (code "190") (name "unconnected-(U1-NRST-Pad69)") (class "Default")
      (node (ref "U1") (pin "69") (pinfunction "NRST_69") (pintype "passive+no_connect"))
    )
    (net (code "191") (name "unconnected-(U1-PB22-Pad141)") (class "Default")
      (node (ref "U1") (pin "141") (pinfunction "PB22_141") (pintype "passive"))
    )
    (net (code "192") (name "unconnected-(U1-PB24-Pad143)") (class "Default")
      (node (ref "U1") (pin "143") (pinfunction "PB24_143") (pintype "passive"))
    )
    (net (code "193") (name "unconnected-(U1-PC10-Pad117)") (class "Default")
      (node (ref "U1") (pin "117") (pinfunction "PC10_117") (pintype "passive"))
    )
    (net (code "194") (name "unconnected-(U1-PC11-Pad93)") (class "Default")
      (node (ref "U1") (pin "93") (pinfunction "PC11_93") (pintype "passive"))
    )
    (net (code "195") (name "unconnected-(U1-PC20-Pad131)") (class "Default")
      (node (ref "U1") (pin "131") (pinfunction "PC20_131") (pintype "passive"))
    )
    (net (code "196") (name "unconnected-(U1-PC27-Pad138)") (class "Default")
      (node (ref "U1") (pin "138") (pinfunction "PC27_138") (pintype "passive"))
    )
    (net (code "197") (name "unconnected-(U1-SHDN-Pad50)") (class "Default")
      (node (ref "U1") (pin "50") (pinfunction "SHDN_50") (pintype "passive+no_connect"))
    )
  )
)
